# Tube_Driver.net
KiCad netlist of a schematic drawn in Altium Designer
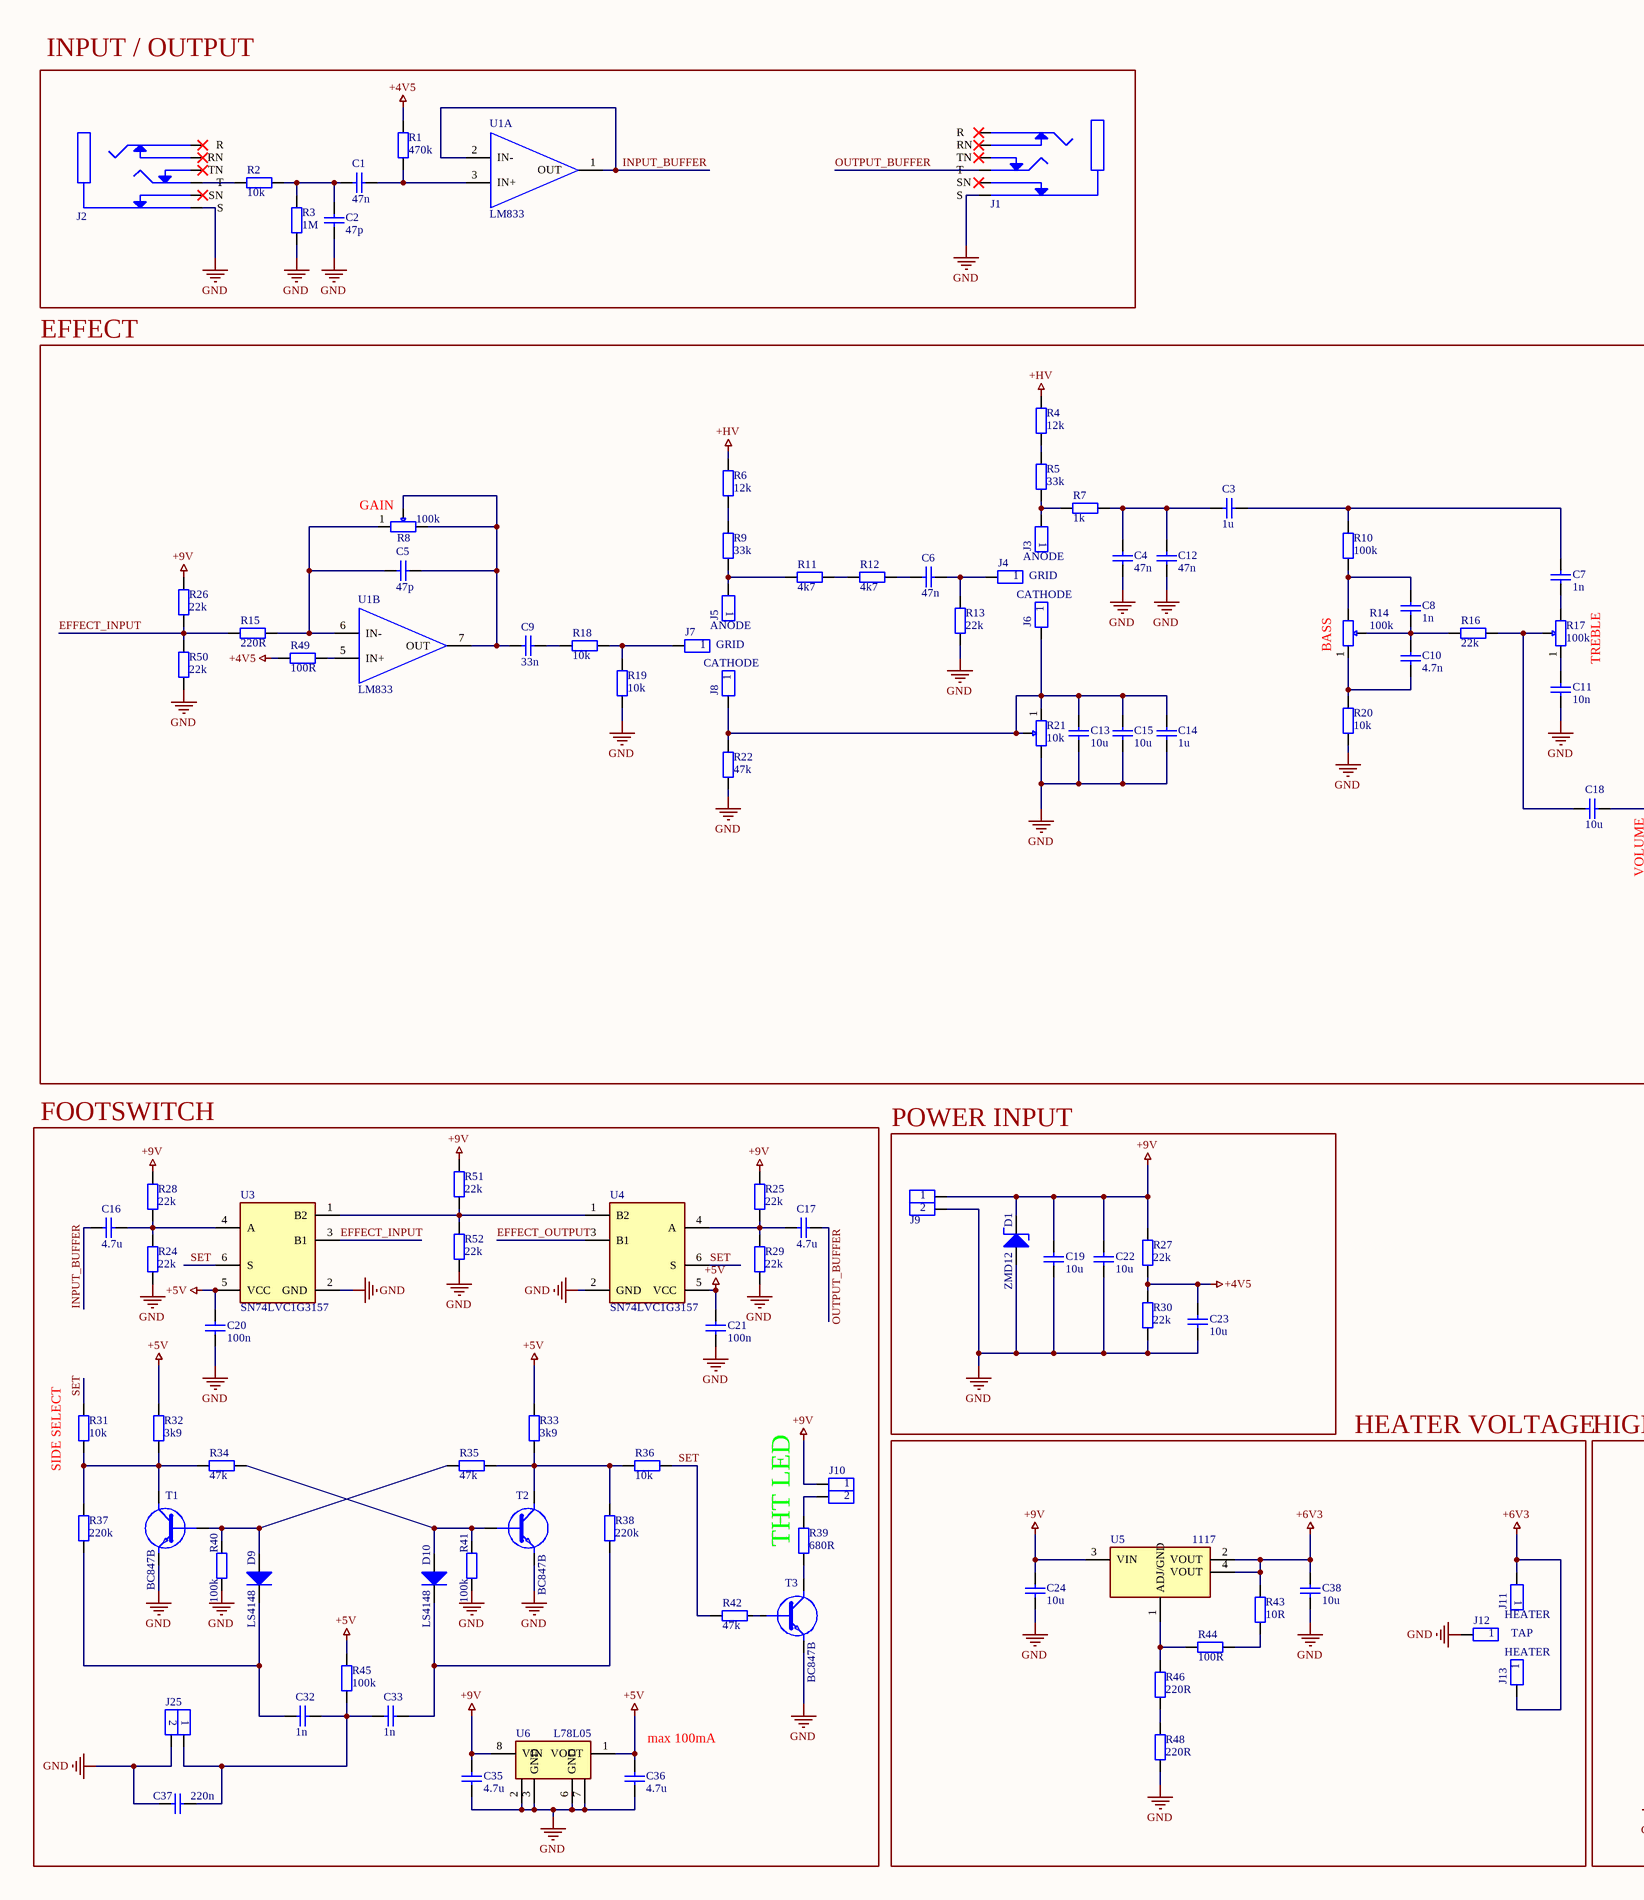
[diagram p0: Tube_Driver.SchDoc, left]
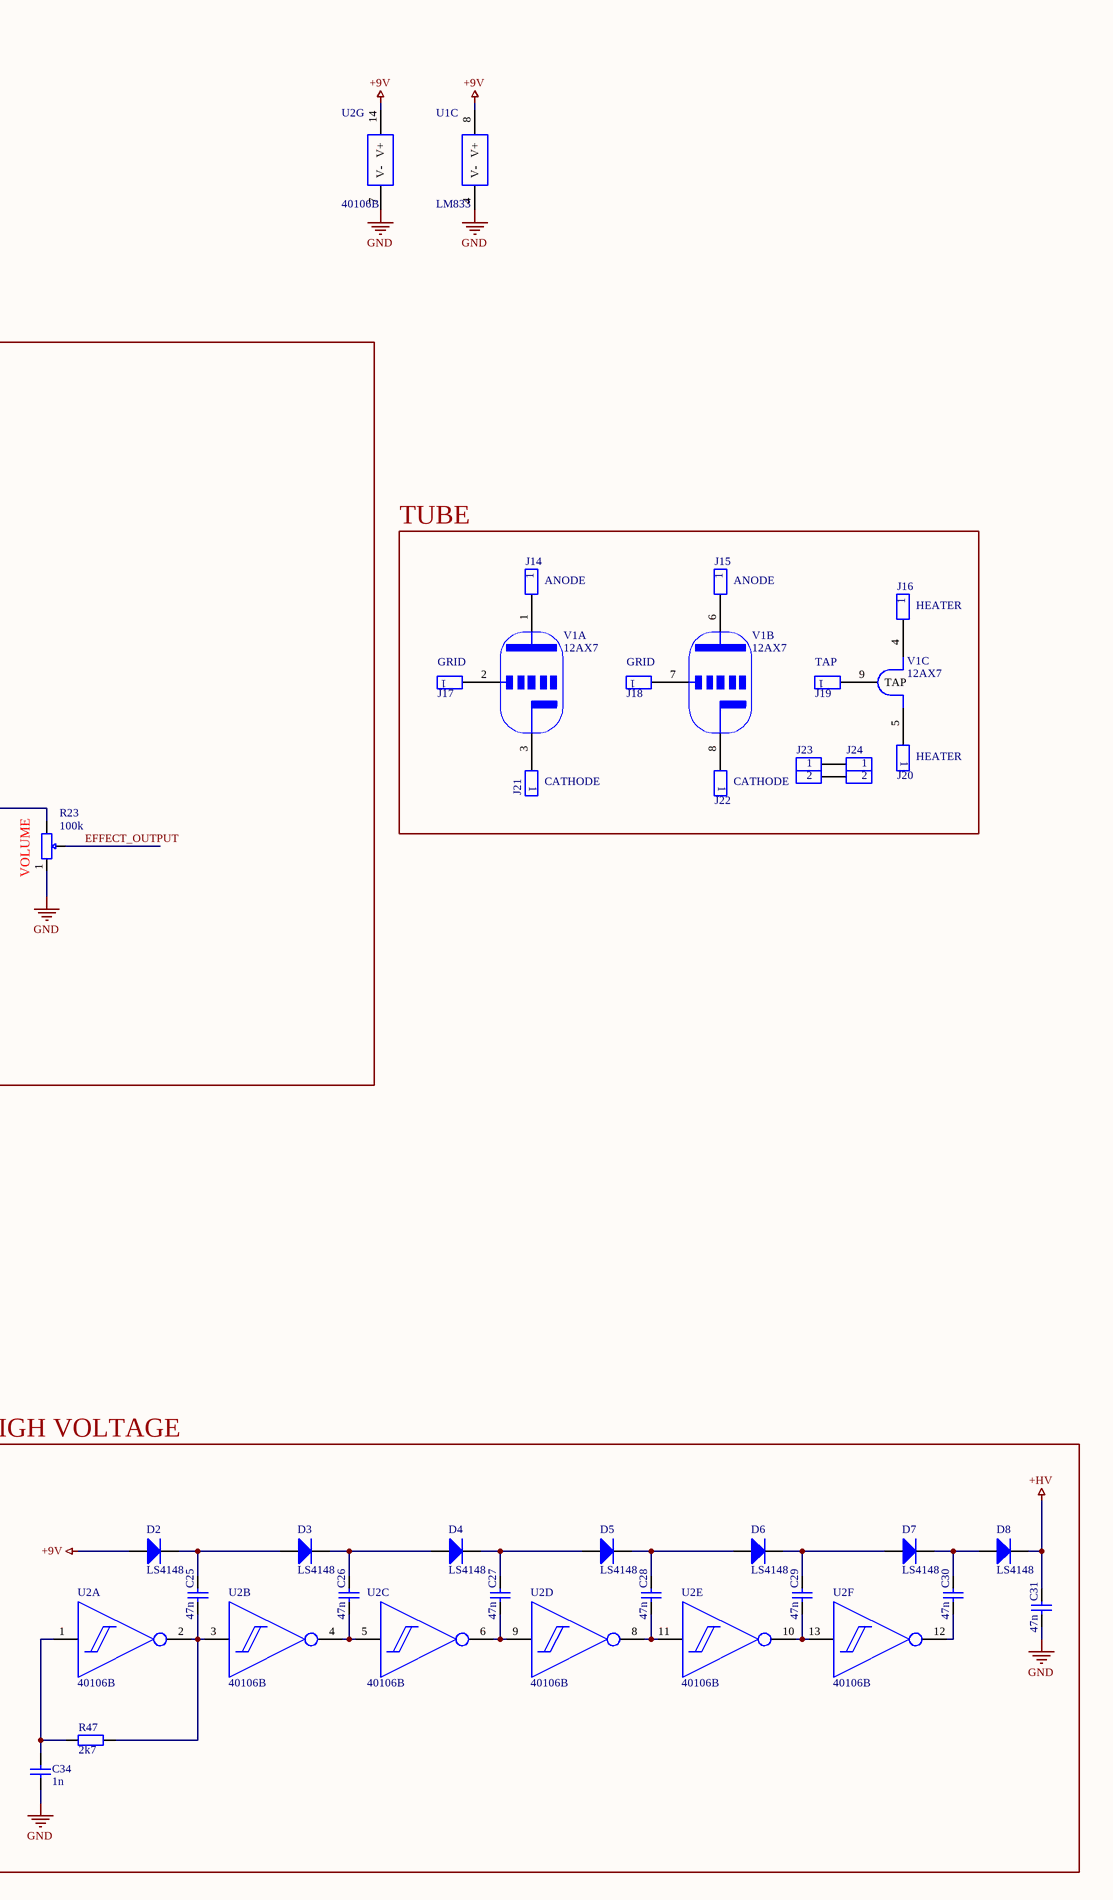
[diagram p1: Tube_Driver.SchDoc, right]

(export (version "E")
  (design (tool "Eeschema 10.0.6"))
  (components
    (comp (ref "C1")
      (value "47n")
      (footprint "TME:CAPACITOR 0805")
      (description "Capacitor: ceramic; MLCC; 47nF; 50V; X7R; ±10%; SMD; 0805")
      (fields
        (field (name "MANUFACTURER") "YAGEO")
        (field (name "MANUFACTURER PART NUMBER") "CC0805KRX7R9BB473")
      )
      (libsource (lib "TME") (part "Capacitor 47n 0805 ±10% SMD E6"))
    )
    (comp (ref "C2")
      (value "47p")
      (footprint "TME:CAPACITOR 0805")
      (description "Capacitor: ceramic; MLCC; 47pF; 50V; C0G (NP0); ±5%; SMD; 0805")
      (fields
        (field (name "MANUFACTURER") "YAGEO")
        (field (name "MANUFACTURER PART NUMBER") "CC0805JRNPO9BN470")
      )
      (libsource (lib "TME") (part "Capacitor 47p 0805 ±5% SMD E6"))
    )
    (comp (ref "C3")
      (value "1u")
      (footprint "TME:CAPACITOR 1206")
      (description "Capacitor: ceramic; MLCC; 1uF; 100V; X7R; ±10%; SMD; 1206")
      (fields
        (field (name "MANUFACTURER") "WALSIN")
        (field (name "MANUFACTURER PART NUMBER") "1206B105K101CT")
      )
      (libsource (lib "TME") (part "Capacitor 1u 1206 ±5% SMD E6"))
    )
    (comp (ref "C4")
      (value "47n")
      (footprint "TME:CAPACITOR 1206")
      (description "Capacitor: ceramic; MLCC; 47nF; 100V; X7R; ±10%; SMD; 1206")
      (fields
        (field (name "MANUFACTURER") "YAGEO")
        (field (name "MANUFACTURER PART NUMBER") "CC1206KRX7R0BB473")
      )
      (libsource (lib "TME") (part "Capacitor 47n 1206 ±10% SMD E6"))
    )
    (comp (ref "C5")
      (value "47p")
      (footprint "TME:CAPACITOR 0805")
      (description "Capacitor: ceramic; MLCC; 47pF; 50V; C0G (NP0); ±5%; SMD; 0805")
      (fields
        (field (name "MANUFACTURER") "YAGEO")
        (field (name "MANUFACTURER PART NUMBER") "CC0805JRNPO9BN470")
      )
      (libsource (lib "TME") (part "Capacitor 47p 0805 ±5% SMD E6"))
    )
    (comp (ref "C6")
      (value "47n")
      (footprint "TME:CAPACITOR 1206")
      (description "Capacitor: ceramic; MLCC; 47nF; 100V; X7R; ±10%; SMD; 1206")
      (fields
        (field (name "MANUFACTURER") "YAGEO")
        (field (name "MANUFACTURER PART NUMBER") "CC1206KRX7R0BB473")
      )
      (libsource (lib "TME") (part "Capacitor 47n 1206 ±10% SMD E6"))
    )
    (comp (ref "C7")
      (value "1n")
      (footprint "TME:CAPACITOR 0805")
      (description "Capacitor: ceramic; MLCC; 1nF; 50V; X7R; ±10%; SMD; 0805")
      (fields
        (field (name "MANUFACTURER") "YAGEO")
        (field (name "MANUFACTURER PART NUMBER") "CC0805KRX7R9BB102")
      )
      (libsource (lib "TME") (part "Capacitor 1n 0805 ±10% SMD E6"))
    )
    (comp (ref "C8")
      (value "1n")
      (footprint "TME:CAPACITOR 0805")
      (description "Capacitor: ceramic; MLCC; 1nF; 50V; X7R; ±10%; SMD; 0805")
      (fields
        (field (name "MANUFACTURER") "YAGEO")
        (field (name "MANUFACTURER PART NUMBER") "CC0805KRX7R9BB102")
      )
      (libsource (lib "TME") (part "Capacitor 1n 0805 ±10% SMD E6"))
    )
    (comp (ref "C9")
      (value "33n")
      (footprint "TME:CAPACITOR 0805")
      (description "Capacitor: ceramic; MLCC; 33nF; 50V; X7R; ±10%; SMD; 0805")
      (fields
        (field (name "MANUFACTURER") "YAGEO")
        (field (name "MANUFACTURER PART NUMBER") "CC0805KRX7R9BB333")
      )
      (libsource (lib "TME") (part "Capacitor 33n 0805 ±10% SMD E6"))
    )
    (comp (ref "C10")
      (value "4.7n")
      (footprint "TME:CAPACITOR 0805")
      (description "Capacitor: ceramic; MLCC; 4.7nF; 50V; X7R; ±10%; SMD; 0805")
      (fields
        (field (name "MANUFACTURER") "YAGEO")
        (field (name "MANUFACTURER PART NUMBER") "CC0805KRX7R9BB472")
      )
      (libsource (lib "TME") (part "Capacitor 4n7 0805 ±10% SMD E6"))
    )
    (comp (ref "C11")
      (value "10n")
      (footprint "TME:CAPACITOR 0805")
      (description "Capacitor: ceramic; MLCC; 10nF; 50V; X7R; ±10%; SMD; 0805")
      (fields
        (field (name "MANUFACTURER") "YAGEO")
        (field (name "MANUFACTURER PART NUMBER") "CC0805KRX7R9BB103")
      )
      (libsource (lib "TME") (part "Capacitor 10n 0805 ±10% SMD E6"))
    )
    (comp (ref "C12")
      (value "47n")
      (footprint "TME:CAPACITOR 1206")
      (description "Capacitor: ceramic; MLCC; 47nF; 100V; X7R; ±10%; SMD; 1206")
      (fields
        (field (name "MANUFACTURER") "YAGEO")
        (field (name "MANUFACTURER PART NUMBER") "CC1206KRX7R0BB473")
      )
      (libsource (lib "TME") (part "Capacitor 47n 1206 ±10% SMD E6"))
    )
    (comp (ref "C13")
      (value "10u")
      (footprint "TME:CAPACITOR 0805")
      (description "Capacitor: ceramic; MLCC; 10uF; 25V; X5R; ±10%; SMD; 0805")
      (fields
        (field (name "MANUFACTURER") "MURATA")
        (field (name "MANUFACTURER PART NUMBER") "GRJ21BR61E106KE01K")
      )
      (libsource (lib "TME") (part "Capacitor 10u 0805 ±10% SMD E3"))
    )
    (comp (ref "C14")
      (value "1u")
      (footprint "TME:CAPACITOR 0805")
      (description "Capacitor: ceramic; MLCC; 1uF; 16V; X7R; ±10%; SMD; 0805")
      (fields
        (field (name "MANUFACTURER") "YAGEO")
        (field (name "MANUFACTURER PART NUMBER") "CC0805KKX7R7BB105")
      )
      (libsource (lib "TME") (part "Capacitor 1u 0805 ±10% SMD E3"))
    )
    (comp (ref "C15")
      (value "10u")
      (footprint "TME:CAPACITOR 0805")
      (description "Capacitor: ceramic; MLCC; 10uF; 25V; X5R; ±10%; SMD; 0805")
      (fields
        (field (name "MANUFACTURER") "MURATA")
        (field (name "MANUFACTURER PART NUMBER") "GRJ21BR61E106KE01K")
      )
      (libsource (lib "TME") (part "Capacitor 10u 0805 ±10% SMD E3"))
    )
    (comp (ref "C16")
      (value "4.7u")
      (footprint "TME:CAPACITOR 0805")
      (description "Capacitor: ceramic; MLCC; 4.7uF; 16V; X7R; ±10%; SMD; 0805")
      (fields
        (field (name "MANUFACTURER") "YAGEO")
        (field (name "MANUFACTURER PART NUMBER") "CC0805KKX7R7BB475")
      )
      (libsource (lib "TME") (part "Capacitor 4u7 0805 ±10% SMD E3"))
    )
    (comp (ref "C17")
      (value "4.7u")
      (footprint "TME:CAPACITOR 0805")
      (description "Capacitor: ceramic; MLCC; 4.7uF; 16V; X7R; ±10%; SMD; 0805")
      (fields
        (field (name "MANUFACTURER") "YAGEO")
        (field (name "MANUFACTURER PART NUMBER") "CC0805KKX7R7BB475")
      )
      (libsource (lib "TME") (part "Capacitor 4u7 0805 ±10% SMD E3"))
    )
    (comp (ref "C18")
      (value "10u")
      (footprint "TME:CAPACITOR 0805")
      (description "Capacitor: ceramic; MLCC; 10uF; 25V; X5R; ±10%; SMD; 0805")
      (fields
        (field (name "MANUFACTURER") "MURATA")
        (field (name "MANUFACTURER PART NUMBER") "GRJ21BR61E106KE01K")
      )
      (libsource (lib "TME") (part "Capacitor 10u 0805 ±10% SMD E3"))
    )
    (comp (ref "C19")
      (value "10u")
      (footprint "TME:CAPACITOR 0805")
      (description "Capacitor: ceramic; MLCC; 10uF; 25V; X5R; ±10%; SMD; 0805")
      (fields
        (field (name "MANUFACTURER") "MURATA")
        (field (name "MANUFACTURER PART NUMBER") "GRJ21BR61E106KE01K")
      )
      (libsource (lib "TME") (part "Capacitor 10u 0805 ±10% SMD E3"))
    )
    (comp (ref "C20")
      (value "100n")
      (footprint "TME:CAPACITOR 0805")
      (description "Capacitor: ceramic; MLCC; 100nF; 50V; X7R; ±10%; SMD; 0805")
      (fields
        (field (name "MANUFACTURER") "YAGEO")
        (field (name "MANUFACTURER PART NUMBER") "CC0805KRX7R9BB104")
      )
      (libsource (lib "TME") (part "Capacitor 100n 0805 ±10% SMD E6"))
    )
    (comp (ref "C21")
      (value "100n")
      (footprint "TME:CAPACITOR 0805")
      (description "Capacitor: ceramic; MLCC; 100nF; 50V; X7R; ±10%; SMD; 0805")
      (fields
        (field (name "MANUFACTURER") "YAGEO")
        (field (name "MANUFACTURER PART NUMBER") "CC0805KRX7R9BB104")
      )
      (libsource (lib "TME") (part "Capacitor 100n 0805 ±10% SMD E6"))
    )
    (comp (ref "C22")
      (value "10u")
      (footprint "TME:CAPACITOR 0805")
      (description "Capacitor: ceramic; MLCC; 10uF; 25V; X5R; ±10%; SMD; 0805")
      (fields
        (field (name "MANUFACTURER") "MURATA")
        (field (name "MANUFACTURER PART NUMBER") "GRJ21BR61E106KE01K")
      )
      (libsource (lib "TME") (part "Capacitor 10u 0805 ±10% SMD E3"))
    )
    (comp (ref "C23")
      (value "10u")
      (footprint "TME:CAPACITOR 0805")
      (description "Capacitor: ceramic; MLCC; 10uF; 25V; X5R; ±10%; SMD; 0805")
      (fields
        (field (name "MANUFACTURER") "MURATA")
        (field (name "MANUFACTURER PART NUMBER") "GRJ21BR61E106KE01K")
      )
      (libsource (lib "TME") (part "Capacitor 10u 0805 ±10% SMD E3"))
    )
    (comp (ref "C24")
      (value "10u")
      (footprint "TME:CAPACITOR 0805")
      (description "Capacitor: ceramic; MLCC; 10uF; 25V; X5R; ±10%; SMD; 0805")
      (fields
        (field (name "MANUFACTURER") "MURATA")
        (field (name "MANUFACTURER PART NUMBER") "GRJ21BR61E106KE01K")
      )
      (libsource (lib "TME") (part "Capacitor 10u 0805 ±10% SMD E3"))
    )
    (comp (ref "C25")
      (value "47n")
      (footprint "TME:CAPACITOR 1206")
      (description "Capacitor: ceramic; MLCC; 47nF; 100V; X7R; ±10%; SMD; 1206")
      (fields
        (field (name "MANUFACTURER") "YAGEO")
        (field (name "MANUFACTURER PART NUMBER") "CC1206KRX7R0BB473")
      )
      (libsource (lib "TME") (part "Capacitor 47n 1206 ±10% SMD E6"))
    )
    (comp (ref "C26")
      (value "47n")
      (footprint "TME:CAPACITOR 1206")
      (description "Capacitor: ceramic; MLCC; 47nF; 100V; X7R; ±10%; SMD; 1206")
      (fields
        (field (name "MANUFACTURER") "YAGEO")
        (field (name "MANUFACTURER PART NUMBER") "CC1206KRX7R0BB473")
      )
      (libsource (lib "TME") (part "Capacitor 47n 1206 ±10% SMD E6"))
    )
    (comp (ref "C27")
      (value "47n")
      (footprint "TME:CAPACITOR 1206")
      (description "Capacitor: ceramic; MLCC; 47nF; 100V; X7R; ±10%; SMD; 1206")
      (fields
        (field (name "MANUFACTURER") "YAGEO")
        (field (name "MANUFACTURER PART NUMBER") "CC1206KRX7R0BB473")
      )
      (libsource (lib "TME") (part "Capacitor 47n 1206 ±10% SMD E6"))
    )
    (comp (ref "C28")
      (value "47n")
      (footprint "TME:CAPACITOR 1206")
      (description "Capacitor: ceramic; MLCC; 47nF; 100V; X7R; ±10%; SMD; 1206")
      (fields
        (field (name "MANUFACTURER") "YAGEO")
        (field (name "MANUFACTURER PART NUMBER") "CC1206KRX7R0BB473")
      )
      (libsource (lib "TME") (part "Capacitor 47n 1206 ±10% SMD E6"))
    )
    (comp (ref "C29")
      (value "47n")
      (footprint "TME:CAPACITOR 1206")
      (description "Capacitor: ceramic; MLCC; 47nF; 100V; X7R; ±10%; SMD; 1206")
      (fields
        (field (name "MANUFACTURER") "YAGEO")
        (field (name "MANUFACTURER PART NUMBER") "CC1206KRX7R0BB473")
      )
      (libsource (lib "TME") (part "Capacitor 47n 1206 ±10% SMD E6"))
    )
    (comp (ref "C30")
      (value "47n")
      (footprint "TME:CAPACITOR 1206")
      (description "Capacitor: ceramic; MLCC; 47nF; 100V; X7R; ±10%; SMD; 1206")
      (fields
        (field (name "MANUFACTURER") "YAGEO")
        (field (name "MANUFACTURER PART NUMBER") "CC1206KRX7R0BB473")
      )
      (libsource (lib "TME") (part "Capacitor 47n 1206 ±10% SMD E6"))
    )
    (comp (ref "C31")
      (value "47n")
      (footprint "TME:CAPACITOR 1206")
      (description "Capacitor: ceramic; MLCC; 47nF; 100V; X7R; ±10%; SMD; 1206")
      (fields
        (field (name "MANUFACTURER") "YAGEO")
        (field (name "MANUFACTURER PART NUMBER") "CC1206KRX7R0BB473")
      )
      (libsource (lib "TME") (part "Capacitor 47n 1206 ±10% SMD E6"))
    )
    (comp (ref "C32")
      (value "1n")
      (footprint "TME:CAPACITOR 0805")
      (description "Capacitor: ceramic; MLCC; 1nF; 50V; X7R; ±10%; SMD; 0805")
      (fields
        (field (name "MANUFACTURER") "YAGEO")
        (field (name "MANUFACTURER PART NUMBER") "CC0805KRX7R9BB102")
      )
      (libsource (lib "TME") (part "Capacitor 1n 0805 ±10% SMD E6"))
    )
    (comp (ref "C33")
      (value "1n")
      (footprint "TME:CAPACITOR 0805")
      (description "Capacitor: ceramic; MLCC; 1nF; 50V; X7R; ±10%; SMD; 0805")
      (fields
        (field (name "MANUFACTURER") "YAGEO")
        (field (name "MANUFACTURER PART NUMBER") "CC0805KRX7R9BB102")
      )
      (libsource (lib "TME") (part "Capacitor 1n 0805 ±10% SMD E6"))
    )
    (comp (ref "C34")
      (value "1n")
      (footprint "TME:CAPACITOR 0805")
      (description "Capacitor: ceramic; MLCC; 1nF; 50V; X7R; ±10%; SMD; 0805")
      (fields
        (field (name "MANUFACTURER") "YAGEO")
        (field (name "MANUFACTURER PART NUMBER") "CC0805KRX7R9BB102")
      )
      (libsource (lib "TME") (part "Capacitor 1n 0805 ±10% SMD E6"))
    )
    (comp (ref "C35")
      (value "4.7u")
      (footprint "TME:CAPACITOR 0805")
      (description "Capacitor: ceramic; MLCC; 4.7uF; 16V; X7R; ±10%; SMD; 0805")
      (fields
        (field (name "MANUFACTURER") "YAGEO")
        (field (name "MANUFACTURER PART NUMBER") "CC0805KKX7R7BB475")
      )
      (libsource (lib "TME") (part "Capacitor 4u7 0805 ±10% SMD E3"))
    )
    (comp (ref "C36")
      (value "4.7u")
      (footprint "TME:CAPACITOR 0805")
      (description "Capacitor: ceramic; MLCC; 4.7uF; 16V; X7R; ±10%; SMD; 0805")
      (fields
        (field (name "MANUFACTURER") "YAGEO")
        (field (name "MANUFACTURER PART NUMBER") "CC0805KKX7R7BB475")
      )
      (libsource (lib "TME") (part "Capacitor 4u7 0805 ±10% SMD E3"))
    )
    (comp (ref "C37")
      (value "220n")
      (footprint "TME:CAPACITOR 0805")
      (description "Capacitor: ceramic; MLCC; 220nF; 50V; X7R; ±10%; SMD; 0805")
      (fields
        (field (name "MANUFACTURER") "YAGEO")
        (field (name "MANUFACTURER PART NUMBER") "CC0805KKX7R9BB224")
      )
      (libsource (lib "TME") (part "Capacitor 220n 0805 ±10% SMD E6"))
    )
    (comp (ref "C38")
      (value "10u")
      (footprint "TME:CAPACITOR 0805")
      (description "Capacitor: ceramic; MLCC; 10uF; 25V; X5R; ±10%; SMD; 0805")
      (fields
        (field (name "MANUFACTURER") "MURATA")
        (field (name "MANUFACTURER PART NUMBER") "GRJ21BR61E106KE01K")
      )
      (libsource (lib "TME") (part "Capacitor 10u 0805 ±10% SMD E3"))
    )
    (comp (ref "D1")
      (value "ZMD12")
      (footprint "TME:DIODE SOD-80 DO-231AA")
      (description "Diode: Zener; 1W; 12V; SMD; reel,tape; MiniMELF plastic")
      (fields (field (name "MANUFACTURER") "DIOTEC SEMICONDUCTOR") (field (name "POWER") "1W"))
      (libsource (lib "TME") (part "Diode 12V 1W SOD80 Zener ZMD12"))
    )
    (comp (ref "D2")
      (value "LS4148")
      (footprint "TME:DIODE SOD-80 DO-231AA")
      (description "Diode: switching; SMD; 100V; 0.15A; 4ns; MiniMELF quadro; Ufmax: 1V")
      (fields (field (name "MANUFACTURER") "DIOTEC SEMICONDUCTOR"))
      (libsource (lib "TME") (part "Diode 100V 0.15A SOD80 General Purpose LL4148"))
    )
    (comp (ref "D3")
      (value "LS4148")
      (footprint "TME:DIODE SOD-80 DO-231AA")
      (description "Diode: switching; SMD; 100V; 0.15A; 4ns; MiniMELF quadro; Ufmax: 1V")
      (fields (field (name "MANUFACTURER") "DIOTEC SEMICONDUCTOR"))
      (libsource (lib "TME") (part "Diode 100V 0.15A SOD80 General Purpose LL4148"))
    )
    (comp (ref "D4")
      (value "LS4148")
      (footprint "TME:DIODE SOD-80 DO-231AA")
      (description "Diode: switching; SMD; 100V; 0.15A; 4ns; MiniMELF quadro; Ufmax: 1V")
      (fields (field (name "MANUFACTURER") "DIOTEC SEMICONDUCTOR"))
      (libsource (lib "TME") (part "Diode 100V 0.15A SOD80 General Purpose LL4148"))
    )
    (comp (ref "D5")
      (value "LS4148")
      (footprint "TME:DIODE SOD-80 DO-231AA")
      (description "Diode: switching; SMD; 100V; 0.15A; 4ns; MiniMELF quadro; Ufmax: 1V")
      (fields (field (name "MANUFACTURER") "DIOTEC SEMICONDUCTOR"))
      (libsource (lib "TME") (part "Diode 100V 0.15A SOD80 General Purpose LL4148"))
    )
    (comp (ref "D6")
      (value "LS4148")
      (footprint "TME:DIODE SOD-80 DO-231AA")
      (description "Diode: switching; SMD; 100V; 0.15A; 4ns; MiniMELF quadro; Ufmax: 1V")
      (fields (field (name "MANUFACTURER") "DIOTEC SEMICONDUCTOR"))
      (libsource (lib "TME") (part "Diode 100V 0.15A SOD80 General Purpose LL4148"))
    )
    (comp (ref "D7")
      (value "LS4148")
      (footprint "TME:DIODE SOD-80 DO-231AA")
      (description "Diode: switching; SMD; 100V; 0.15A; 4ns; MiniMELF quadro; Ufmax: 1V")
      (fields (field (name "MANUFACTURER") "DIOTEC SEMICONDUCTOR"))
      (libsource (lib "TME") (part "Diode 100V 0.15A SOD80 General Purpose LL4148"))
    )
    (comp (ref "D8")
      (value "LS4148")
      (footprint "TME:DIODE SOD-80 DO-231AA")
      (description "Diode: switching; SMD; 100V; 0.15A; 4ns; MiniMELF quadro; Ufmax: 1V")
      (fields (field (name "MANUFACTURER") "DIOTEC SEMICONDUCTOR"))
      (libsource (lib "TME") (part "Diode 100V 0.15A SOD80 General Purpose LL4148"))
    )
    (comp (ref "D9")
      (value "LS4148")
      (footprint "TME:DIODE SOD-80 DO-231AA")
      (description "Diode: switching; SMD; 100V; 0.15A; 4ns; MiniMELF quadro; Ufmax: 1V")
      (fields (field (name "MANUFACTURER") "DIOTEC SEMICONDUCTOR"))
      (libsource (lib "TME") (part "Diode 100V 0.15A SOD80 General Purpose LL4148"))
    )
    (comp (ref "D10")
      (value "LS4148")
      (footprint "TME:DIODE SOD-80 DO-231AA")
      (description "Diode: switching; SMD; 100V; 0.15A; 4ns; MiniMELF quadro; Ufmax: 1V")
      (fields (field (name "MANUFACTURER") "DIOTEC SEMICONDUCTOR"))
      (libsource (lib "TME") (part "Diode 100V 0.15A SOD80 General Purpose LL4148"))
    )
    (comp (ref "J1")
      (value "ACJM-IH")
      (footprint "TME:AMPHENOL ACJM-MHDR")
      (description "Socket; Jack 6,3mm; female; mono,with double switch; ways: 2; THT")
      (fields (field (name "MANUFACTURER") "AMPHENOL"))
      (libsource (lib "TME") (part "Mechanical Jack 6.3mm Socket PCB THT ACJM-MHDR"))
    )
    (comp (ref "J2")
      (value "ACJM-IH")
      (footprint "TME:AMPHENOL ACJM-MHDR")
      (description "Socket; Jack 6,3mm; female; mono,with double switch; ways: 2; THT")
      (fields (field (name "MANUFACTURER") "AMPHENOL"))
      (libsource (lib "TME") (part "Mechanical Jack 6.3mm Socket PCB THT ACJM-MHDR"))
    )
    (comp (ref "J3")
      (value "901200761")
      (footprint "TME:MECHANICAL PINHEADER 1P 2.54MM MALE")
      (description "Pin header; pin strips; C-Grid III; male; PIN: 1; straight; 2.54mm")
      (fields (field (name "MANUFACTURER") "MOLEX"))
      (libsource (lib "TME") (part "Mechanical Pinheader Male 1pin P=2.54mm THT"))
    )
    (comp (ref "J4")
      (value "901200761")
      (footprint "TME:MECHANICAL PINHEADER 1P 2.54MM MALE")
      (description "Pin header; pin strips; C-Grid III; male; PIN: 1; straight; 2.54mm")
      (fields (field (name "MANUFACTURER") "MOLEX"))
      (libsource (lib "") (part "Mechanical Pinheader Male 1pin P=2.54mm THT_3"))
    )
    (comp (ref "J5")
      (value "901200761")
      (footprint "TME:MECHANICAL PINHEADER 1P 2.54MM MALE")
      (description "Pin header; pin strips; C-Grid III; male; PIN: 1; straight; 2.54mm")
      (fields (field (name "MANUFACTURER") "MOLEX"))
      (libsource (lib "TME") (part "Mechanical Pinheader Male 1pin P=2.54mm THT"))
    )
    (comp (ref "J6")
      (value "901200761")
      (footprint "TME:MECHANICAL PINHEADER 1P 2.54MM MALE")
      (description "Pin header; pin strips; C-Grid III; male; PIN: 1; straight; 2.54mm")
      (fields (field (name "MANUFACTURER") "MOLEX"))
      (libsource (lib "") (part "Mechanical Pinheader Male 1pin P=2.54mm THT_1"))
    )
    (comp (ref "J7")
      (value "901200761")
      (footprint "TME:MECHANICAL PINHEADER 1P 2.54MM MALE")
      (description "Pin header; pin strips; C-Grid III; male; PIN: 1; straight; 2.54mm")
      (fields (field (name "MANUFACTURER") "MOLEX"))
      (libsource (lib "") (part "Mechanical Pinheader Male 1pin P=2.54mm THT_3"))
    )
    (comp (ref "J8")
      (value "901200761")
      (footprint "TME:MECHANICAL PINHEADER 1P 2.54MM MALE")
      (description "Pin header; pin strips; C-Grid III; male; PIN: 1; straight; 2.54mm")
      (fields (field (name "MANUFACTURER") "MOLEX"))
      (libsource (lib "") (part "Mechanical Pinheader Male 1pin P=2.54mm THT_1"))
    )
    (comp (ref "J9")
      (value "901200762")
      (footprint "TME:MECHANICAL PINHEADER 2P 2.54MM MALE")
      (description "Pin header; pin strips; C-Grid III; male; PIN: 2; straight; 2.54mm")
      (fields (field (name "MANUFACTURER") "MOLEX"))
      (libsource (lib "") (part "Mechanical Pinheader Male 2pin P=2.54mm THT_1"))
    )
    (comp (ref "J10")
      (value "901200762")
      (footprint "TME:MECHANICAL PINHEADER 2P 2.54MM MALE")
      (description "Pin header; pin strips; C-Grid III; male; PIN: 2; straight; 2.54mm")
      (fields (field (name "MANUFACTURER") "MOLEX"))
      (libsource (lib "TME") (part "Mechanical Pinheader Male 2pin P=2.54mm THT"))
    )
    (comp (ref "J11")
      (value "901200761")
      (footprint "TME:MECHANICAL PINHEADER 1P 2.54MM MALE")
      (description "Pin header; pin strips; C-Grid III; male; PIN: 1; straight; 2.54mm")
      (fields (field (name "MANUFACTURER") "MOLEX"))
      (libsource (lib "TME") (part "Mechanical Pinheader Male 1pin P=2.54mm THT"))
    )
    (comp (ref "J12")
      (value "901200761")
      (footprint "TME:MECHANICAL PINHEADER 1P 2.54MM MALE")
      (description "Pin header; pin strips; C-Grid III; male; PIN: 1; straight; 2.54mm")
      (fields (field (name "MANUFACTURER") "MOLEX"))
      (libsource (lib "") (part "Mechanical Pinheader Male 1pin P=2.54mm THT_3"))
    )
    (comp (ref "J13")
      (value "901200761")
      (footprint "TME:MECHANICAL PINHEADER 1P 2.54MM MALE")
      (description "Pin header; pin strips; C-Grid III; male; PIN: 1; straight; 2.54mm")
      (fields (field (name "MANUFACTURER") "MOLEX"))
      (libsource (lib "") (part "Mechanical Pinheader Male 1pin P=2.54mm THT_1"))
    )
    (comp (ref "J14")
      (value "901200761")
      (footprint "TME:MECHANICAL PINHEADER 1P 2.54MM MALE")
      (description "Pin header; pin strips; C-Grid III; male; PIN: 1; straight; 2.54mm")
      (fields (field (name "MANUFACTURER") "MOLEX"))
      (libsource (lib "") (part "Mechanical Pinheader Male 1pin P=2.54mm THT_1"))
    )
    (comp (ref "J15")
      (value "901200761")
      (footprint "TME:MECHANICAL PINHEADER 1P 2.54MM MALE")
      (description "Pin header; pin strips; C-Grid III; male; PIN: 1; straight; 2.54mm")
      (fields (field (name "MANUFACTURER") "MOLEX"))
      (libsource (lib "") (part "Mechanical Pinheader Male 1pin P=2.54mm THT_1"))
    )
    (comp (ref "J16")
      (value "901200761")
      (footprint "TME:MECHANICAL PINHEADER 1P 2.54MM MALE")
      (description "Pin header; pin strips; C-Grid III; male; PIN: 1; straight; 2.54mm")
      (fields (field (name "MANUFACTURER") "MOLEX"))
      (libsource (lib "") (part "Mechanical Pinheader Male 1pin P=2.54mm THT_1"))
    )
    (comp (ref "J17")
      (value "901200761")
      (footprint "TME:MECHANICAL PINHEADER 1P 2.54MM MALE")
      (description "Pin header; pin strips; C-Grid III; male; PIN: 1; straight; 2.54mm")
      (fields (field (name "MANUFACTURER") "MOLEX"))
      (libsource (lib "") (part "Mechanical Pinheader Male 1pin P=2.54mm THT_2"))
    )
    (comp (ref "J18")
      (value "901200761")
      (footprint "TME:MECHANICAL PINHEADER 1P 2.54MM MALE")
      (description "Pin header; pin strips; C-Grid III; male; PIN: 1; straight; 2.54mm")
      (fields (field (name "MANUFACTURER") "MOLEX"))
      (libsource (lib "") (part "Mechanical Pinheader Male 1pin P=2.54mm THT_2"))
    )
    (comp (ref "J19")
      (value "901200761")
      (footprint "TME:MECHANICAL PINHEADER 1P 2.54MM MALE")
      (description "Pin header; pin strips; C-Grid III; male; PIN: 1; straight; 2.54mm")
      (fields (field (name "MANUFACTURER") "MOLEX"))
      (libsource (lib "") (part "Mechanical Pinheader Male 1pin P=2.54mm THT_2"))
    )
    (comp (ref "J20")
      (value "901200761")
      (footprint "TME:MECHANICAL PINHEADER 1P 2.54MM MALE")
      (description "Pin header; pin strips; C-Grid III; male; PIN: 1; straight; 2.54mm")
      (fields (field (name "MANUFACTURER") "MOLEX"))
      (libsource (lib "TME") (part "Mechanical Pinheader Male 1pin P=2.54mm THT"))
    )
    (comp (ref "J21")
      (value "901200761")
      (footprint "TME:MECHANICAL PINHEADER 1P 2.54MM MALE")
      (description "Pin header; pin strips; C-Grid III; male; PIN: 1; straight; 2.54mm")
      (fields (field (name "MANUFACTURER") "MOLEX"))
      (libsource (lib "TME") (part "Mechanical Pinheader Male 1pin P=2.54mm THT"))
    )
    (comp (ref "J22")
      (value "901200761")
      (footprint "TME:MECHANICAL PINHEADER 1P 2.54MM MALE")
      (description "Pin header; pin strips; C-Grid III; male; PIN: 1; straight; 2.54mm")
      (fields (field (name "MANUFACTURER") "MOLEX"))
      (libsource (lib "TME") (part "Mechanical Pinheader Male 1pin P=2.54mm THT"))
    )
    (comp (ref "J23")
      (value "901200762")
      (footprint "TME:MECHANICAL PINHEADER 2P 2.54MM MALE")
      (description "Pin header; pin strips; C-Grid III; male; PIN: 2; straight; 2.54mm")
      (fields (field (name "MANUFACTURER") "MOLEX"))
      (libsource (lib "") (part "Mechanical Pinheader Male 2pin P=2.54mm THT_1"))
    )
    (comp (ref "J24")
      (value "901200762")
      (footprint "TME:MECHANICAL PINHEADER 2P 2.54MM MALE")
      (description "Pin header; pin strips; C-Grid III; male; PIN: 2; straight; 2.54mm")
      (fields (field (name "MANUFACTURER") "MOLEX"))
      (libsource (lib "TME") (part "Mechanical Pinheader Male 2pin P=2.54mm THT"))
    )
    (comp (ref "J25")
      (value "901200762")
      (footprint "TME:MECHANICAL PINHEADER 2P 2.54MM MALE")
      (description "Pin header; pin strips; C-Grid III; male; PIN: 2; straight; 2.54mm")
      (fields (field (name "MANUFACTURER") "MOLEX"))
      (libsource (lib "TME") (part "Mechanical Pinheader Male 2pin P=2.54mm THT"))
    )
    (comp (ref "R1")
      (value "470k")
      (footprint "TME:RESISTOR 0805")
      (description "Resistor: thick film; SMD; 0805; 470kΩ; 0,125W; ±1%; -55÷155°C")
      (fields
        (field (name "MANUFACTURER") "YAGEO")
        (field (name "MANUFACTURER PART NUMBER") "RC0805FR-07470KL")
      )
      (libsource (lib "TME") (part "Resistor 470k 0805 1% 0.125W SMD E12"))
    )
    (comp (ref "R2")
      (value "10k")
      (footprint "TME:RESISTOR 0805")
      (description "Resistor: thick film; SMD; 0805; 10kΩ; 0,125W; ±1%; -55÷155°C")
      (fields
        (field (name "MANUFACTURER") "YAGEO")
        (field (name "MANUFACTURER PART NUMBER") "RC0805FR-0710KL")
      )
      (libsource (lib "") (part "Resistor 10k 0805 1% 0.125W SMD E12_1"))
    )
    (comp (ref "R3")
      (value "1M")
      (footprint "TME:RESISTOR 0805")
      (description "Resistor: thick film; SMD; 0805; 1MΩ; 0,125W; ±1%; -55÷155°C")
      (fields
        (field (name "MANUFACTURER") "YAGEO")
        (field (name "MANUFACTURER PART NUMBER") "RC0805FR-071ML")
      )
      (libsource (lib "TME") (part "Resistor 1M 0805 1% 0.125W SMD E12"))
    )
    (comp (ref "R4")
      (value "12k")
      (footprint "TME:RESISTOR 0805")
      (description "Resistor: thick film; SMD; 0805; 12kΩ; 0,125W; ±1%; -55÷155°C")
      (fields
        (field (name "MANUFACTURER") "YAGEO")
        (field (name "MANUFACTURER PART NUMBER") "RC0805FR-0712KL")
      )
      (libsource (lib "TME") (part "Resistor 12k 0805 1% 0.125W SMD E12"))
    )
    (comp (ref "R5")
      (value "33k")
      (footprint "TME:RESISTOR 0805")
      (description "Resistor: thick film; SMD; 0805; 33kΩ; 0,125W; ±1%; -55÷155°C")
      (fields
        (field (name "MANUFACTURER") "YAGEO")
        (field (name "MANUFACTURER PART NUMBER") "RC0805FR-0733KL")
      )
      (libsource (lib "TME") (part "Resistor 33k 0805 1% 0.125W SMD E12"))
    )
    (comp (ref "R6")
      (value "12k")
      (footprint "TME:RESISTOR 0805")
      (description "Resistor: thick film; SMD; 0805; 12kΩ; 0,125W; ±1%; -55÷155°C")
      (fields
        (field (name "MANUFACTURER") "YAGEO")
        (field (name "MANUFACTURER PART NUMBER") "RC0805FR-0712KL")
      )
      (libsource (lib "TME") (part "Resistor 12k 0805 1% 0.125W SMD E12"))
    )
    (comp (ref "R7")
      (value "1k")
      (footprint "TME:RESISTOR 0805")
      (description "Resistor: thick film; SMD; 0805; 1kΩ; 0,125W; ±1%; -55÷155°C")
      (fields
        (field (name "MANUFACTURER") "YAGEO")
        (field (name "MANUFACTURER PART NUMBER") "RC0805FR-071KL")
      )
      (libsource (lib "TME") (part "Resistor 1k 0805 1% 0.125W SMD E12"))
    )
    (comp (ref "R8")
      (value "100k")
      (footprint "TME:POTENTIOMETER PTV09A")
      (description "Potentiometer: shaft; single turn; 100kΩ; 125mW; ±20%; THT; 6mm")
      (fields
        (field (name "MANUFACTURER") "SR PASSIVES")
        (field (name "MANUFACTURER PART NUMBER") "R9011-1-100K")
      )
      (libsource (lib "") (part "Potentiometer PCB 100k THT Linear PTV09A_1"))
    )
    (comp (ref "R9")
      (value "33k")
      (footprint "TME:RESISTOR 0805")
      (description "Resistor: thick film; SMD; 0805; 33kΩ; 0,125W; ±1%; -55÷155°C")
      (fields
        (field (name "MANUFACTURER") "YAGEO")
        (field (name "MANUFACTURER PART NUMBER") "RC0805FR-0733KL")
      )
      (libsource (lib "TME") (part "Resistor 33k 0805 1% 0.125W SMD E12"))
    )
    (comp (ref "R10")
      (value "100k")
      (footprint "TME:RESISTOR 0805")
      (description "Resistor: thick film; SMD; 0805; 100kΩ; 0,125W; ±1%; -55÷155°C")
      (fields
        (field (name "MANUFACTURER") "YAGEO")
        (field (name "MANUFACTURER PART NUMBER") "RC0805FR-07100KL")
      )
      (libsource (lib "TME") (part "Resistor 100k 0805 1% 0.125W SMD E12"))
    )
    (comp (ref "R11")
      (value "4k7")
      (footprint "TME:RESISTOR 0805")
      (description "Resistor: thick film; SMD; 0805; 4.7kΩ; 0,125W; ±1%; -55÷155°C")
      (fields
        (field (name "MANUFACTURER") "YAGEO")
        (field (name "MANUFACTURER PART NUMBER") "RC0805FR-074K7L")
      )
      (libsource (lib "TME") (part "Resistor 4k7 0805 1% 0.125W SMD E12"))
    )
    (comp (ref "R12")
      (value "4k7")
      (footprint "TME:RESISTOR 0805")
      (description "Resistor: thick film; SMD; 0805; 4.7kΩ; 0,125W; ±1%; -55÷155°C")
      (fields
        (field (name "MANUFACTURER") "YAGEO")
        (field (name "MANUFACTURER PART NUMBER") "RC0805FR-074K7L")
      )
      (libsource (lib "TME") (part "Resistor 4k7 0805 1% 0.125W SMD E12"))
    )
    (comp (ref "R13")
      (value "22k")
      (footprint "TME:RESISTOR 0805")
      (description "Resistor: thick film; SMD; 0805; 22kΩ; 0,125W; ±1%; -55÷155°C")
      (fields
        (field (name "MANUFACTURER") "YAGEO")
        (field (name "MANUFACTURER PART NUMBER") "RC0805FR-0722KL")
      )
      (libsource (lib "TME") (part "Resistor 22k 0805 1% 0.125W SMD E12"))
    )
    (comp (ref "R14")
      (value "100k")
      (footprint "TME:POTENTIOMETER PTV09A")
      (description "Potentiometer: shaft; single turn; 100kΩ; 125mW; ±20%; THT; 6mm")
      (fields
        (field (name "MANUFACTURER") "SR PASSIVES")
        (field (name "MANUFACTURER PART NUMBER") "R9011-1-100K")
      )
      (libsource (lib "") (part "Potentiometer PCB 100k THT Linear PTV09A_1"))
    )
    (comp (ref "R15")
      (value "220R")
      (footprint "TME:RESISTOR 0805")
      (description "Resistor: thick film; SMD; 0805; 220Ω; 0,125W; ±1%; -55÷155°C")
      (fields
        (field (name "MANUFACTURER") "YAGEO")
        (field (name "MANUFACTURER PART NUMBER") "RC0805FR-07220RL")
      )
      (libsource (lib "") (part "Resistor 220R 0805 1% 0.125W SMD E12_1"))
    )
    (comp (ref "R16")
      (value "22k")
      (footprint "TME:RESISTOR 0805")
      (description "Resistor: thick film; SMD; 0805; 22kΩ; 0,125W; ±1%; -55÷155°C")
      (fields
        (field (name "MANUFACTURER") "YAGEO")
        (field (name "MANUFACTURER PART NUMBER") "RC0805FR-0722KL")
      )
      (libsource (lib "") (part "Resistor 22k 0805 1% 0.125W SMD E12_1"))
    )
    (comp (ref "R17")
      (value "100k")
      (footprint "TME:POTENTIOMETER PTV09A")
      (description "Potentiometer: shaft; single turn; 100kΩ; 125mW; ±20%; THT; 6mm")
      (fields
        (field (name "MANUFACTURER") "SR PASSIVES")
        (field (name "MANUFACTURER PART NUMBER") "R9011-1-100K")
      )
      (libsource (lib "TME") (part "Potentiometer PCB 100k THT Linear PTV09A"))
    )
    (comp (ref "R18")
      (value "10k")
      (footprint "TME:RESISTOR 0805")
      (description "Resistor: thick film; SMD; 0805; 10kΩ; 0,125W; ±1%; -55÷155°C")
      (fields
        (field (name "MANUFACTURER") "YAGEO")
        (field (name "MANUFACTURER PART NUMBER") "RC0805FR-0710KL")
      )
      (libsource (lib "") (part "Resistor 10k 0805 1% 0.125W SMD E12_1"))
    )
    (comp (ref "R19")
      (value "10k")
      (footprint "TME:RESISTOR 0805")
      (description "Resistor: thick film; SMD; 0805; 10kΩ; 0,125W; ±1%; -55÷155°C")
      (fields
        (field (name "MANUFACTURER") "YAGEO")
        (field (name "MANUFACTURER PART NUMBER") "RC0805FR-0710KL")
      )
      (libsource (lib "TME") (part "Resistor 10k 0805 1% 0.125W SMD E12"))
    )
    (comp (ref "R20")
      (value "10k")
      (footprint "TME:RESISTOR 0805")
      (description "Resistor: thick film; SMD; 0805; 10kΩ; 0,125W; ±1%; -55÷155°C")
      (fields
        (field (name "MANUFACTURER") "YAGEO")
        (field (name "MANUFACTURER PART NUMBER") "RC0805FR-0710KL")
      )
      (libsource (lib "TME") (part "Resistor 10k 0805 1% 0.125W SMD E12"))
    )
    (comp (ref "R21")
      (value "10k")
      (footprint "TME:Potentiometer 3x3.5x1.55mm")
      (description "Potentiometer: mounting; single turn; 10kΩ; 100mW; SMD; ±25%; linear")
      (fields
        (field (name "MANUFACTURER") "SR PASSIVES")
        (field (name "MANUFACTURER PART NUMBER") "3305SMD-10K")
      )
      (libsource (lib "TME") (part "Potentiometer 10k 25% 0.1W SMD Linear 3x3.5x1.55mm"))
    )
    (comp (ref "R22")
      (value "47k")
      (footprint "TME:RESISTOR 0805")
      (description "Resistor: thick film; SMD; 0805; 47kΩ; 0,125W; ±1%; -55÷155°C")
      (fields
        (field (name "MANUFACTURER") "YAGEO")
        (field (name "MANUFACTURER PART NUMBER") "RC0805FR-0747KL")
      )
      (libsource (lib "") (part "Resistor 47k 0805 1% 0.125W SMD E12_1"))
    )
    (comp (ref "R23")
      (value "100k")
      (footprint "TME:POTENTIOMETER PTV09A")
      (description "Potentiometer: shaft; single turn; 100kΩ; 125mW; ±20%; THT; 6mm")
      (fields
        (field (name "MANUFACTURER") "SR PASSIVES")
        (field (name "MANUFACTURER PART NUMBER") "R9011-1-100K")
      )
      (libsource (lib "") (part "Potentiometer PCB 100k THT Linear PTV09A_1"))
    )
    (comp (ref "R24")
      (value "22k")
      (footprint "TME:RESISTOR 0805")
      (description "Resistor: thick film; SMD; 0805; 22kΩ; 0,125W; ±1%; -55÷155°C")
      (fields
        (field (name "MANUFACTURER") "YAGEO")
        (field (name "MANUFACTURER PART NUMBER") "RC0805FR-0722KL")
      )
      (libsource (lib "TME") (part "Resistor 22k 0805 1% 0.125W SMD E12"))
    )
    (comp (ref "R25")
      (value "22k")
      (footprint "TME:RESISTOR 0805")
      (description "Resistor: thick film; SMD; 0805; 22kΩ; 0,125W; ±1%; -55÷155°C")
      (fields
        (field (name "MANUFACTURER") "YAGEO")
        (field (name "MANUFACTURER PART NUMBER") "RC0805FR-0722KL")
      )
      (libsource (lib "TME") (part "Resistor 22k 0805 1% 0.125W SMD E12"))
    )
    (comp (ref "R26")
      (value "22k")
      (footprint "TME:RESISTOR 0805")
      (description "Resistor: thick film; SMD; 0805; 22kΩ; 0,125W; ±1%; -55÷155°C")
      (fields
        (field (name "MANUFACTURER") "YAGEO")
        (field (name "MANUFACTURER PART NUMBER") "RC0805FR-0722KL")
      )
      (libsource (lib "TME") (part "Resistor 22k 0805 1% 0.125W SMD E12"))
    )
    (comp (ref "R27")
      (value "22k")
      (footprint "TME:RESISTOR 0805")
      (description "Resistor: thick film; SMD; 0805; 22kΩ; 0,125W; ±1%; -55÷155°C")
      (fields
        (field (name "MANUFACTURER") "YAGEO")
        (field (name "MANUFACTURER PART NUMBER") "RC0805FR-0722KL")
      )
      (libsource (lib "TME") (part "Resistor 22k 0805 1% 0.125W SMD E12"))
    )
    (comp (ref "R28")
      (value "22k")
      (footprint "TME:RESISTOR 0805")
      (description "Resistor: thick film; SMD; 0805; 22kΩ; 0,125W; ±1%; -55÷155°C")
      (fields
        (field (name "MANUFACTURER") "YAGEO")
        (field (name "MANUFACTURER PART NUMBER") "RC0805FR-0722KL")
      )
      (libsource (lib "TME") (part "Resistor 22k 0805 1% 0.125W SMD E12"))
    )
    (comp (ref "R29")
      (value "22k")
      (footprint "TME:RESISTOR 0805")
      (description "Resistor: thick film; SMD; 0805; 22kΩ; 0,125W; ±1%; -55÷155°C")
      (fields
        (field (name "MANUFACTURER") "YAGEO")
        (field (name "MANUFACTURER PART NUMBER") "RC0805FR-0722KL")
      )
      (libsource (lib "TME") (part "Resistor 22k 0805 1% 0.125W SMD E12"))
    )
    (comp (ref "R30")
      (value "22k")
      (footprint "TME:RESISTOR 0805")
      (description "Resistor: thick film; SMD; 0805; 22kΩ; 0,125W; ±1%; -55÷155°C")
      (fields
        (field (name "MANUFACTURER") "YAGEO")
        (field (name "MANUFACTURER PART NUMBER") "RC0805FR-0722KL")
      )
      (libsource (lib "TME") (part "Resistor 22k 0805 1% 0.125W SMD E12"))
    )
    (comp (ref "R31")
      (value "10k")
      (footprint "TME:RESISTOR 0805")
      (description "Resistor: thick film; SMD; 0805; 10kΩ; 0,125W; ±1%; -55÷155°C")
      (fields
        (field (name "MANUFACTURER") "YAGEO")
        (field (name "MANUFACTURER PART NUMBER") "RC0805FR-0710KL")
      )
      (libsource (lib "TME") (part "Resistor 10k 0805 1% 0.125W SMD E12"))
    )
    (comp (ref "R32")
      (value "3k9")
      (footprint "TME:RESISTOR 0805")
      (description "Resistor: thick film; SMD; 0805; 3.9kΩ; 0,125W; ±1%; -55÷155°C")
      (fields
        (field (name "MANUFACTURER") "YAGEO")
        (field (name "MANUFACTURER PART NUMBER") "RC0805FR-073K9L")
      )
      (libsource (lib "TME") (part "Resistor 3K9 0805 1% 0.125W SMD E12"))
    )
    (comp (ref "R33")
      (value "3k9")
      (footprint "TME:RESISTOR 0805")
      (description "Resistor: thick film; SMD; 0805; 3.9kΩ; 0,125W; ±1%; -55÷155°C")
      (fields
        (field (name "MANUFACTURER") "YAGEO")
        (field (name "MANUFACTURER PART NUMBER") "RC0805FR-073K9L")
      )
      (libsource (lib "TME") (part "Resistor 3K9 0805 1% 0.125W SMD E12"))
    )
    (comp (ref "R34")
      (value "47k")
      (footprint "TME:RESISTOR 0805")
      (description "Resistor: thick film; SMD; 0805; 47kΩ; 0,125W; ±1%; -55÷155°C")
      (fields
        (field (name "MANUFACTURER") "YAGEO")
        (field (name "MANUFACTURER PART NUMBER") "RC0805FR-0747KL")
      )
      (libsource (lib "TME") (part "Resistor 47k 0805 1% 0.125W SMD E12"))
    )
    (comp (ref "R35")
      (value "47k")
      (footprint "TME:RESISTOR 0805")
      (description "Resistor: thick film; SMD; 0805; 47kΩ; 0,125W; ±1%; -55÷155°C")
      (fields
        (field (name "MANUFACTURER") "YAGEO")
        (field (name "MANUFACTURER PART NUMBER") "RC0805FR-0747KL")
      )
      (libsource (lib "TME") (part "Resistor 47k 0805 1% 0.125W SMD E12"))
    )
    (comp (ref "R36")
      (value "10k")
      (footprint "TME:RESISTOR 0805")
      (description "Resistor: thick film; SMD; 0805; 10kΩ; 0,125W; ±1%; -55÷155°C")
      (fields
        (field (name "MANUFACTURER") "YAGEO")
        (field (name "MANUFACTURER PART NUMBER") "RC0805FR-0710KL")
      )
      (libsource (lib "") (part "Resistor 10k 0805 1% 0.125W SMD E12_1"))
    )
    (comp (ref "R37")
      (value "220k")
      (footprint "TME:RESISTOR 0805")
      (description "Resistor: thick film; SMD; 0805; 220kΩ; 0,125W; ±1%; -55÷155°C")
      (fields
        (field (name "MANUFACTURER") "YAGEO")
        (field (name "MANUFACTURER PART NUMBER") "RC0805FR-07220KL")
      )
      (libsource (lib "TME") (part "Resistor 220k 0805 1% 0.125W SMD E12"))
    )
    (comp (ref "R38")
      (value "220k")
      (footprint "TME:RESISTOR 0805")
      (description "Resistor: thick film; SMD; 0805; 220kΩ; 0,125W; ±1%; -55÷155°C")
      (fields
        (field (name "MANUFACTURER") "YAGEO")
        (field (name "MANUFACTURER PART NUMBER") "RC0805FR-07220KL")
      )
      (libsource (lib "TME") (part "Resistor 220k 0805 1% 0.125W SMD E12"))
    )
    (comp (ref "R39")
      (value "680R")
      (footprint "TME:RESISTOR 0805")
      (description "Resistor: thick film; SMD; 0805; 680Ω; 0,125W; ±1%; -55÷155°C")
      (fields
        (field (name "MANUFACTURER") "YAGEO")
        (field (name "MANUFACTURER PART NUMBER") "RC0805FR-07680RL")
      )
      (libsource (lib "TME") (part "Resistor 680R 0805 1% 0.125W SMD E12"))
    )
    (comp (ref "R40")
      (value "100k")
      (footprint "TME:RESISTOR 0805")
      (description "Resistor: thick film; SMD; 0805; 100kΩ; 0,125W; ±1%; -55÷155°C")
      (fields
        (field (name "MANUFACTURER") "YAGEO")
        (field (name "MANUFACTURER PART NUMBER") "RC0805FR-07100KL")
      )
      (libsource (lib "TME") (part "Resistor 100k 0805 1% 0.125W SMD E12"))
    )
    (comp (ref "R41")
      (value "100k")
      (footprint "TME:RESISTOR 0805")
      (description "Resistor: thick film; SMD; 0805; 100kΩ; 0,125W; ±1%; -55÷155°C")
      (fields
        (field (name "MANUFACTURER") "YAGEO")
        (field (name "MANUFACTURER PART NUMBER") "RC0805FR-07100KL")
      )
      (libsource (lib "TME") (part "Resistor 100k 0805 1% 0.125W SMD E12"))
    )
    (comp (ref "R42")
      (value "47k")
      (footprint "TME:RESISTOR 0805")
      (description "Resistor: thick film; SMD; 0805; 47kΩ; 0,125W; ±1%; -55÷155°C")
      (fields
        (field (name "MANUFACTURER") "YAGEO")
        (field (name "MANUFACTURER PART NUMBER") "RC0805FR-0747KL")
      )
      (libsource (lib "TME") (part "Resistor 47k 0805 1% 0.125W SMD E12"))
    )
    (comp (ref "R43")
      (value "10R")
      (footprint "TME:RESISTOR 0805")
      (description "Resistor: thick film; SMD; 0805; 10Ω; 0,125W; ±1%; -55÷155°C")
      (fields
        (field (name "MANUFACTURER") "YAGEO")
        (field (name "MANUFACTURER PART NUMBER") "RC0805FR-0710RL")
      )
      (libsource (lib "TME") (part "Resistor 10R 0805 1% 0.125W SMD E12"))
    )
    (comp (ref "R44")
      (value "100R")
      (footprint "TME:RESISTOR 0805")
      (description "Resistor: thick film; SMD; 0805; 10Ω; 0,125W; ±1%; -55÷155°C")
      (fields
        (field (name "MANUFACTURER") "YAGEO")
        (field (name "MANUFACTURER PART NUMBER") "RC0805FR-07100RL")
      )
      (libsource (lib "TME") (part "Resistor 100R 0805 1% 0.125W SMD E12"))
    )
    (comp (ref "R45")
      (value "100k")
      (footprint "TME:RESISTOR 0805")
      (description "Resistor: thick film; SMD; 0805; 100kΩ; 0,125W; ±1%; -55÷155°C")
      (fields
        (field (name "MANUFACTURER") "YAGEO")
        (field (name "MANUFACTURER PART NUMBER") "RC0805FR-07100KL")
      )
      (libsource (lib "TME") (part "Resistor 100k 0805 1% 0.125W SMD E12"))
    )
    (comp (ref "R46")
      (value "220R")
      (footprint "TME:RESISTOR 0805")
      (description "Resistor: thick film; SMD; 0805; 220Ω; 0,125W; ±1%; -55÷155°C")
      (fields
        (field (name "MANUFACTURER") "YAGEO")
        (field (name "MANUFACTURER PART NUMBER") "RC0805FR-07220RL")
      )
      (libsource (lib "TME") (part "Resistor 220R 0805 1% 0.125W SMD E12"))
    )
    (comp (ref "R47")
      (value "2k7")
      (footprint "TME:RESISTOR 0805")
      (description "Resistor: thick film; SMD; 0805; 2.7kΩ; 0,125W; ±1%; -55÷155°C")
      (fields
        (field (name "MANUFACTURER") "YAGEO")
        (field (name "MANUFACTURER PART NUMBER") "RC0805FR-072K7L")
      )
      (libsource (lib "TME") (part "Resistor 2k7 0805 1% 0.125W SMD E12"))
    )
    (comp (ref "R48")
      (value "220R")
      (footprint "TME:RESISTOR 0805")
      (description "Resistor: thick film; SMD; 0805; 220Ω; 0,125W; ±1%; -55÷155°C")
      (fields
        (field (name "MANUFACTURER") "YAGEO")
        (field (name "MANUFACTURER PART NUMBER") "RC0805FR-07220RL")
      )
      (libsource (lib "TME") (part "Resistor 220R 0805 1% 0.125W SMD E12"))
    )
    (comp (ref "R49")
      (value "100R")
      (footprint "TME:RESISTOR 0805")
      (description "Resistor: thick film; SMD; 0805; 10Ω; 0,125W; ±1%; -55÷155°C")
      (fields
        (field (name "MANUFACTURER") "YAGEO")
        (field (name "MANUFACTURER PART NUMBER") "RC0805FR-07100RL")
      )
      (libsource (lib "TME") (part "Resistor 100R 0805 1% 0.125W SMD E12"))
    )
    (comp (ref "R50")
      (value "22k")
      (footprint "TME:RESISTOR 0805")
      (description "Resistor: thick film; SMD; 0805; 22kΩ; 0,125W; ±1%; -55÷155°C")
      (fields
        (field (name "MANUFACTURER") "YAGEO")
        (field (name "MANUFACTURER PART NUMBER") "RC0805FR-0722KL")
      )
      (libsource (lib "TME") (part "Resistor 22k 0805 1% 0.125W SMD E12"))
    )
    (comp (ref "R51")
      (value "22k")
      (footprint "TME:RESISTOR 0805")
      (description "Resistor: thick film; SMD; 0805; 22kΩ; 0,125W; ±1%; -55÷155°C")
      (fields
        (field (name "MANUFACTURER") "YAGEO")
        (field (name "MANUFACTURER PART NUMBER") "RC0805FR-0722KL")
      )
      (libsource (lib "TME") (part "Resistor 22k 0805 1% 0.125W SMD E12"))
    )
    (comp (ref "R52")
      (value "22k")
      (footprint "TME:RESISTOR 0805")
      (description "Resistor: thick film; SMD; 0805; 22kΩ; 0,125W; ±1%; -55÷155°C")
      (fields
        (field (name "MANUFACTURER") "YAGEO")
        (field (name "MANUFACTURER PART NUMBER") "RC0805FR-0722KL")
      )
      (libsource (lib "TME") (part "Resistor 22k 0805 1% 0.125W SMD E12"))
    )
    (comp (ref "T1")
      (value "BC847B")
      (footprint "TME:SOT23-3")
      (description "Transistor: NPN; bipolar; 50V; 0.1A; 0.225W; SOT23")
      (fields (field (name "MANUFACTURER") "ONSEMI") (field (name "MANUFACTURER PART NUMBER") "BC847BLT1G"))
      (libsource (lib "TME") (part "Transistor NPN 100mA 50V 0.225W BC847BLT1G"))
    )
    (comp (ref "T2")
      (value "BC847B")
      (footprint "TME:SOT23-3")
      (description "Transistor: NPN; bipolar; 50V; 0.1A; 0.225W; SOT23")
      (fields (field (name "MANUFACTURER") "ONSEMI") (field (name "MANUFACTURER PART NUMBER") "BC847BLT1G"))
      (libsource (lib "TME") (part "Transistor NPN 100mA 50V 0.225W BC847BLT1G"))
    )
    (comp (ref "T3")
      (value "BC847B")
      (footprint "TME:SOT23-3")
      (description "Transistor: NPN; bipolar; 50V; 0.1A; 0.225W; SOT23")
      (fields (field (name "MANUFACTURER") "ONSEMI") (field (name "MANUFACTURER PART NUMBER") "BC847BLT1G"))
      (libsource (lib "TME") (part "Transistor NPN 100mA 50V 0.225W BC847BLT1G"))
    )
    (comp (ref "U1")
      (value "LM833")
      (footprint "TME:SOIC-8")
      (description "Audio Amplifiers SOIC8 5-36V 15MHz LM833")
      (fields
        (field (name "MANUFACTURER") "STMicroelectronics")
        (field (name "MANUFACTURER PART NUMBER") "LM833DT")
      )
      (libsource (lib "TME") (part "IC Op-Amp Dual LM833DT SOIC-8"))
    )
    (comp (ref "U2")
      (value "40106B")
      (footprint "TME:SOIC-14")
      (description "IC: digital; NOT; Ch: 6; IN: 1; CMOS; SMD; SOIC14; 3÷18VDC; -55÷125°C")
      (fields
        (field (name "MANUFACTURER") "TEXAS INSTRUMENTS")
        (field (name "MANUFACTURER PART NUMBER") "LM833DT")
      )
      (libsource (lib "TME") (part "IC Gate NOT Schmitt 6CH SOIC14"))
    )
    (comp (ref "U3")
      (value "SN74LVC1G3157")
      (footprint "TME:SOT23-6")
      (description "IC: analog switch; SPDT; Ch: 1; SOT23-6; 1.65÷5.5VDC")
      (fields
        (field (name "MANUFACTURER") "TEXAS INSTRUMENTS")
        (field (name "MANUFACTURER PART NUMBER") "SN74LVC1G3157DBVR")
      )
      (libsource (lib "TME") (part "IC SPDT Analog Switch SOT-23-6 SN74LVC1G3157DBVR"))
    )
    (comp (ref "U4")
      (value "SN74LVC1G3157")
      (footprint "TME:SOT23-6")
      (description "IC: analog switch; SPDT; Ch: 1; SOT23-6; 1.65÷5.5VDC")
      (fields
        (field (name "MANUFACTURER") "TEXAS INSTRUMENTS")
        (field (name "MANUFACTURER PART NUMBER") "SN74LVC1G3157DBVR")
      )
      (libsource (lib "") (part "IC SPDT Analog Switch SOT-23-6 SN74LVC1G3157DBVR_1"))
    )
    (comp (ref "U5")
      (value "1117")
      (footprint "TME:SOT223")
      (description "IC: voltage regulator; LDO,linear,adjustable; 1.25÷13.65V; 1A")
      (fields
        (field (name "MANUFACTURER") "DIOTEC SEMICONDUCTOR")
        (field (name "MANUFACTURER PART NUMBER") "LDI1117-ADH")
      )
      (libsource (lib "TME") (part "IC LDO ADJ 1A SOT223 SMD LDI1117"))
    )
    (comp (ref "U6")
      (value "L78L05")
      (footprint "TME:SOIC-8")
      (description "IC: voltage regulator; linear,fixed; 5V; 0.1A; SO8; SMD; reel,tape")
      (fields
        (field (name "MANUFACTURER") "STMicroelectronics")
        (field (name "MANUFACTURER PART NUMBER") "L78L05CD13TR")
      )
      (libsource (lib "TME") (part "IC LDO 5V 0.1A SO8 SMD L78L05CD13TR"))
    )
    (comp (ref "V1")
      (value "12AX7")
      (footprint "TME:TUbe 9pin NOVAL")
      (libsource (lib "") (part "Tube 12AX7 / ECC83 9pin NOVAL_1"))
    )
  )
  (nets
    (net (code "1") (name "+4V5") (class "Default")
      (node (ref "C23") (pin "2") (pinfunction "2_2") (pintype "passive"))
      (node (ref "R1") (pin "2") (pinfunction "2_2") (pintype "passive"))
      (node (ref "R27") (pin "1") (pinfunction "1_1") (pintype "passive"))
      (node (ref "R30") (pin "2") (pinfunction "2_2") (pintype "passive"))
      (node (ref "R49") (pin "1") (pinfunction "1_1") (pintype "passive"))
    )
    (net (code "2") (name "+5V") (class "Default")
      (node (ref "C20") (pin "2") (pinfunction "2_2") (pintype "passive"))
      (node (ref "C21") (pin "2") (pinfunction "2_2") (pintype "passive"))
      (node (ref "C36") (pin "2") (pinfunction "2_2") (pintype "passive"))
      (node (ref "R32") (pin "2") (pinfunction "2_2") (pintype "passive"))
      (node (ref "R33") (pin "2") (pinfunction "2_2") (pintype "passive"))
      (node (ref "R45") (pin "2") (pinfunction "2_2") (pintype "passive"))
      (node (ref "U3") (pin "5") (pinfunction "VCC_5") (pintype "power_in"))
      (node (ref "U4") (pin "5") (pinfunction "VCC_5") (pintype "power_in"))
      (node (ref "U6") (pin "1") (pinfunction "VOUT_1") (pintype "passive"))
    )
    (net (code "3") (name "+6V3") (class "Default")
      (node (ref "C38") (pin "2") (pinfunction "2_2") (pintype "passive"))
      (node (ref "J11") (pin "1") (pinfunction "1_1") (pintype "passive"))
      (node (ref "J13") (pin "1") (pinfunction "1_1") (pintype "passive"))
      (node (ref "R43") (pin "2") (pinfunction "2_2") (pintype "passive"))
      (node (ref "U5") (pin "2") (pinfunction "VOUT_2") (pintype "passive"))
      (node (ref "U5") (pin "4") (pinfunction "VOUT_4") (pintype "passive"))
    )
    (net (code "4") (name "+9V") (class "Default")
      (node (ref "C19") (pin "2") (pinfunction "2_2") (pintype "passive"))
      (node (ref "C22") (pin "2") (pinfunction "2_2") (pintype "passive"))
      (node (ref "C24") (pin "2") (pinfunction "2_2") (pintype "passive"))
      (node (ref "C35") (pin "2") (pinfunction "2_2") (pintype "passive"))
      (node (ref "D1") (pin "2") (pinfunction "2_2") (pintype "passive"))
      (node (ref "D2") (pin "1") (pinfunction "1_1") (pintype "passive"))
      (node (ref "J10") (pin "1") (pinfunction "1_1") (pintype "passive"))
      (node (ref "J9") (pin "1") (pinfunction "1_1") (pintype "passive"))
      (node (ref "R25") (pin "2") (pinfunction "2_2") (pintype "passive"))
      (node (ref "R26") (pin "2") (pinfunction "2_2") (pintype "passive"))
      (node (ref "R27") (pin "2") (pinfunction "2_2") (pintype "passive"))
      (node (ref "R28") (pin "2") (pinfunction "2_2") (pintype "passive"))
      (node (ref "R51") (pin "2") (pinfunction "2_2") (pintype "passive"))
      (node (ref "U1") (pin "8") (pinfunction "V+_8") (pintype "passive"))
      (node (ref "U2") (pin "14") (pinfunction "V+_14") (pintype "passive"))
      (node (ref "U5") (pin "3") (pinfunction "VIN_3") (pintype "passive"))
      (node (ref "U6") (pin "8") (pinfunction "VIN_8") (pintype "passive"))
    )
    (net (code "5") (name "+HV") (class "Default")
      (node (ref "C31") (pin "2") (pinfunction "2_2") (pintype "passive"))
      (node (ref "D8") (pin "2") (pinfunction "2_2") (pintype "passive"))
      (node (ref "R4") (pin "2") (pinfunction "2_2") (pintype "passive"))
      (node (ref "R6") (pin "2") (pinfunction "2_2") (pintype "passive"))
    )
    (net (code "6") (name "/EFFECT_INPUT") (class "Default")
      (node (ref "R15") (pin "1") (pinfunction "1_1") (pintype "passive"))
      (node (ref "R26") (pin "1") (pinfunction "1_1") (pintype "passive"))
      (node (ref "R50") (pin "2") (pinfunction "2_2") (pintype "passive"))
      (node (ref "U3") (pin "3") (pinfunction "B1_3") (pintype "passive"))
    )
    (net (code "7") (name "/EFFECT_OUTPUT") (class "Default")
      (node (ref "R23") (pin "2") (pinfunction "2_2") (pintype "passive"))
      (node (ref "U4") (pin "3") (pinfunction "B1_3") (pintype "passive"))
    )
    (net (code "8") (name "/INPUT_BUFFER") (class "Default")
      (node (ref "C16") (pin "1") (pinfunction "1_1") (pintype "passive"))
      (node (ref "U1") (pin "1") (pinfunction "OUT_1") (pintype "passive"))
      (node (ref "U1") (pin "2") (pinfunction "IN-_2") (pintype "passive"))
    )
    (net (code "9") (name "/OUTPUT_BUFFER") (class "Default")
      (node (ref "C17") (pin "2") (pinfunction "2_2") (pintype "passive"))
      (node (ref "J1") (pin "3") (pinfunction "T_3") (pintype "passive"))
    )
    (net (code "10") (name "/SET") (class "Default")
      (node (ref "R31") (pin "2") (pinfunction "2_2") (pintype "passive"))
      (node (ref "R36") (pin "2") (pinfunction "2_2") (pintype "passive"))
      (node (ref "R42") (pin "1") (pinfunction "1_1") (pintype "passive"))
      (node (ref "U3") (pin "6") (pinfunction "S_6") (pintype "passive"))
      (node (ref "U4") (pin "6") (pinfunction "S_6") (pintype "passive"))
    )
    (net (code "11") (name "GND") (class "Default")
      (node (ref "C11") (pin "1") (pinfunction "1_1") (pintype "passive"))
      (node (ref "C12") (pin "1") (pinfunction "1_1") (pintype "passive"))
      (node (ref "C13") (pin "1") (pinfunction "1_1") (pintype "passive"))
      (node (ref "C14") (pin "1") (pinfunction "1_1") (pintype "passive"))
      (node (ref "C15") (pin "1") (pinfunction "1_1") (pintype "passive"))
      (node (ref "C19") (pin "1") (pinfunction "1_1") (pintype "passive"))
      (node (ref "C2") (pin "1") (pinfunction "1_1") (pintype "passive"))
      (node (ref "C20") (pin "1") (pinfunction "1_1") (pintype "passive"))
      (node (ref "C21") (pin "1") (pinfunction "1_1") (pintype "passive"))
      (node (ref "C22") (pin "1") (pinfunction "1_1") (pintype "passive"))
      (node (ref "C23") (pin "1") (pinfunction "1_1") (pintype "passive"))
      (node (ref "C24") (pin "1") (pinfunction "1_1") (pintype "passive"))
      (node (ref "C31") (pin "1") (pinfunction "1_1") (pintype "passive"))
      (node (ref "C34") (pin "1") (pinfunction "1_1") (pintype "passive"))
      (node (ref "C35") (pin "1") (pinfunction "1_1") (pintype "passive"))
      (node (ref "C36") (pin "1") (pinfunction "1_1") (pintype "passive"))
      (node (ref "C37") (pin "1") (pinfunction "1_1") (pintype "passive"))
      (node (ref "C38") (pin "1") (pinfunction "1_1") (pintype "passive"))
      (node (ref "C4") (pin "1") (pinfunction "1_1") (pintype "passive"))
      (node (ref "D1") (pin "1") (pinfunction "1_1") (pintype "passive"))
      (node (ref "J1") (pin "1") (pinfunction "S_1") (pintype "passive"))
      (node (ref "J12") (pin "1") (pinfunction "1_1") (pintype "passive"))
      (node (ref "J2") (pin "1") (pinfunction "S_1") (pintype "passive"))
      (node (ref "J25") (pin "2") (pinfunction "2_2") (pintype "passive"))
      (node (ref "J9") (pin "2") (pinfunction "2_2") (pintype "passive"))
      (node (ref "R13") (pin "1") (pinfunction "1_1") (pintype "passive"))
      (node (ref "R19") (pin "1") (pinfunction "1_1") (pintype "passive"))
      (node (ref "R20") (pin "1") (pinfunction "1_1") (pintype "passive"))
      (node (ref "R21") (pin "3") (pinfunction "3_3") (pintype "passive"))
      (node (ref "R22") (pin "1") (pinfunction "1_1") (pintype "passive"))
      (node (ref "R23") (pin "1") (pinfunction "1_1") (pintype "passive"))
      (node (ref "R24") (pin "1") (pinfunction "1_1") (pintype "passive"))
      (node (ref "R29") (pin "1") (pinfunction "1_1") (pintype "passive"))
      (node (ref "R3") (pin "2") (pinfunction "2_2") (pintype "passive"))
      (node (ref "R30") (pin "1") (pinfunction "1_1") (pintype "passive"))
      (node (ref "R40") (pin "1") (pinfunction "1_1") (pintype "passive"))
      (node (ref "R41") (pin "1") (pinfunction "1_1") (pintype "passive"))
      (node (ref "R48") (pin "1") (pinfunction "1_1") (pintype "passive"))
      (node (ref "R50") (pin "1") (pinfunction "1_1") (pintype "passive"))
      (node (ref "R52") (pin "1") (pinfunction "1_1") (pintype "passive"))
      (node (ref "T1") (pin "2") (pinfunction "E_2") (pintype "passive"))
      (node (ref "T2") (pin "2") (pinfunction "E_2") (pintype "passive"))
      (node (ref "T3") (pin "2") (pinfunction "E_2") (pintype "passive"))
      (node (ref "U1") (pin "4") (pinfunction "V-_4") (pintype "passive"))
      (node (ref "U2") (pin "7") (pinfunction "V-_7") (pintype "passive"))
      (node (ref "U3") (pin "2") (pinfunction "GND_2") (pintype "power_in"))
      (node (ref "U4") (pin "2") (pinfunction "GND_2") (pintype "power_in"))
      (node (ref "U6") (pin "2") (pinfunction "GND_2") (pintype "passive"))
      (node (ref "U6") (pin "3") (pinfunction "GND_3") (pintype "passive"))
      (node (ref "U6") (pin "6") (pinfunction "GND_6") (pintype "passive"))
      (node (ref "U6") (pin "7") (pinfunction "GND_7") (pintype "passive"))
    )
    (net (code "12") (name "Net-(C1-Pad1)") (class "Default")
      (node (ref "C1") (pin "1") (pinfunction "1_1") (pintype "passive"))
      (node (ref "C2") (pin "2") (pinfunction "2_2") (pintype "passive"))
      (node (ref "R2") (pin "2") (pinfunction "2_2") (pintype "passive"))
      (node (ref "R3") (pin "1") (pinfunction "1_1") (pintype "passive"))
    )
    (net (code "13") (name "Net-(C3-Pad2)") (class "Default")
      (node (ref "C3") (pin "2") (pinfunction "2_2") (pintype "passive"))
      (node (ref "C7") (pin "2") (pinfunction "2_2") (pintype "passive"))
      (node (ref "R10") (pin "2") (pinfunction "2_2") (pintype "passive"))
    )
    (net (code "14") (name "Net-(C6-Pad1)") (class "Default")
      (node (ref "C6") (pin "1") (pinfunction "1_1") (pintype "passive"))
      (node (ref "R12") (pin "2") (pinfunction "2_2") (pintype "passive"))
    )
    (net (code "15") (name "Net-(C6-Pad2)") (class "Default")
      (node (ref "C6") (pin "2") (pinfunction "2_2") (pintype "passive"))
      (node (ref "J4") (pin "1") (pinfunction "1_1") (pintype "passive"))
      (node (ref "R13") (pin "2") (pinfunction "2_2") (pintype "passive"))
    )
    (net (code "16") (name "Net-(C7-Pad1)") (class "Default")
      (node (ref "C7") (pin "1") (pinfunction "1_1") (pintype "passive"))
      (node (ref "R17") (pin "3") (pinfunction "3_3") (pintype "passive"))
    )
    (net (code "17") (name "Net-(C8-Pad2)") (class "Default")
      (node (ref "C8") (pin "2") (pinfunction "2_2") (pintype "passive"))
      (node (ref "R10") (pin "1") (pinfunction "1_1") (pintype "passive"))
      (node (ref "R14") (pin "3") (pinfunction "3_3") (pintype "passive"))
    )
    (net (code "18") (name "Net-(C9-Pad2)") (class "Default")
      (node (ref "C9") (pin "2") (pinfunction "2_2") (pintype "passive"))
      (node (ref "R18") (pin "1") (pinfunction "1_1") (pintype "passive"))
    )
    (net (code "19") (name "Net-(C10-Pad1)") (class "Default")
      (node (ref "C10") (pin "1") (pinfunction "1_1") (pintype "passive"))
      (node (ref "R14") (pin "1") (pinfunction "1_1") (pintype "passive"))
      (node (ref "R20") (pin "2") (pinfunction "2_2") (pintype "passive"))
    )
    (net (code "20") (name "Net-(C10-Pad2)") (class "Default")
      (node (ref "C10") (pin "2") (pinfunction "2_2") (pintype "passive"))
      (node (ref "C8") (pin "1") (pinfunction "1_1") (pintype "passive"))
      (node (ref "R14") (pin "2") (pinfunction "2_2") (pintype "passive"))
      (node (ref "R16") (pin "1") (pinfunction "1_1") (pintype "passive"))
    )
    (net (code "21") (name "Net-(C11-Pad2)") (class "Default")
      (node (ref "C11") (pin "2") (pinfunction "2_2") (pintype "passive"))
      (node (ref "R17") (pin "1") (pinfunction "1_1") (pintype "passive"))
    )
    (net (code "22") (name "Net-(C12-Pad2)") (class "Default")
      (node (ref "C12") (pin "2") (pinfunction "2_2") (pintype "passive"))
      (node (ref "C3") (pin "1") (pinfunction "1_1") (pintype "passive"))
      (node (ref "C4") (pin "2") (pinfunction "2_2") (pintype "passive"))
      (node (ref "R7") (pin "2") (pinfunction "2_2") (pintype "passive"))
    )
    (net (code "23") (name "Net-(C13-Pad2)") (class "Default")
      (node (ref "C13") (pin "2") (pinfunction "2_2") (pintype "passive"))
      (node (ref "C14") (pin "2") (pinfunction "2_2") (pintype "passive"))
      (node (ref "C15") (pin "2") (pinfunction "2_2") (pintype "passive"))
      (node (ref "J6") (pin "1") (pinfunction "1_1") (pintype "passive"))
      (node (ref "J8") (pin "1") (pinfunction "1_1") (pintype "passive"))
      (node (ref "R21") (pin "1") (pinfunction "1_1") (pintype "passive"))
      (node (ref "R21") (pin "2") (pinfunction "2_2") (pintype "passive"))
      (node (ref "R22") (pin "2") (pinfunction "2_2") (pintype "passive"))
    )
    (net (code "24") (name "Net-(C18-Pad1)") (class "Default")
      (node (ref "C18") (pin "1") (pinfunction "1_1") (pintype "passive"))
      (node (ref "R23") (pin "3") (pinfunction "3_3") (pintype "passive"))
    )
    (net (code "25") (name "Net-(C18-Pad2)") (class "Default")
      (node (ref "C18") (pin "2") (pinfunction "2_2") (pintype "passive"))
      (node (ref "R16") (pin "2") (pinfunction "2_2") (pintype "passive"))
      (node (ref "R17") (pin "2") (pinfunction "2_2") (pintype "passive"))
    )
    (net (code "26") (name "Net-(C25-Pad2)") (class "Default")
      (node (ref "C25") (pin "2") (pinfunction "2_2") (pintype "passive"))
      (node (ref "D2") (pin "2") (pinfunction "2_2") (pintype "passive"))
      (node (ref "D3") (pin "1") (pinfunction "1_1") (pintype "passive"))
    )
    (net (code "27") (name "Net-(C26-Pad2)") (class "Default")
      (node (ref "C26") (pin "2") (pinfunction "2_2") (pintype "passive"))
      (node (ref "D3") (pin "2") (pinfunction "2_2") (pintype "passive"))
      (node (ref "D4") (pin "1") (pinfunction "1_1") (pintype "passive"))
    )
    (net (code "28") (name "Net-(C27-Pad2)") (class "Default")
      (node (ref "C27") (pin "2") (pinfunction "2_2") (pintype "passive"))
      (node (ref "D4") (pin "2") (pinfunction "2_2") (pintype "passive"))
      (node (ref "D5") (pin "1") (pinfunction "1_1") (pintype "passive"))
    )
    (net (code "29") (name "Net-(C28-Pad2)") (class "Default")
      (node (ref "C28") (pin "2") (pinfunction "2_2") (pintype "passive"))
      (node (ref "D5") (pin "2") (pinfunction "2_2") (pintype "passive"))
      (node (ref "D6") (pin "1") (pinfunction "1_1") (pintype "passive"))
    )
    (net (code "30") (name "Net-(C29-Pad2)") (class "Default")
      (node (ref "C29") (pin "2") (pinfunction "2_2") (pintype "passive"))
      (node (ref "D6") (pin "2") (pinfunction "2_2") (pintype "passive"))
      (node (ref "D7") (pin "1") (pinfunction "1_1") (pintype "passive"))
    )
    (net (code "31") (name "Net-(C30-Pad2)") (class "Default")
      (node (ref "C30") (pin "2") (pinfunction "2_2") (pintype "passive"))
      (node (ref "D7") (pin "2") (pinfunction "2_2") (pintype "passive"))
      (node (ref "D8") (pin "1") (pinfunction "1_1") (pintype "passive"))
    )
    (net (code "32") (name "Net-(C32-Pad1)") (class "Default")
      (node (ref "C32") (pin "1") (pinfunction "1_1") (pintype "passive"))
      (node (ref "D9") (pin "2") (pinfunction "2_2") (pintype "passive"))
      (node (ref "R37") (pin "1") (pinfunction "1_1") (pintype "passive"))
    )
    (net (code "33") (name "Net-(C32-Pad2)") (class "Default")
      (node (ref "C32") (pin "2") (pinfunction "2_2") (pintype "passive"))
      (node (ref "C33") (pin "1") (pinfunction "1_1") (pintype "passive"))
      (node (ref "C37") (pin "2") (pinfunction "2_2") (pintype "passive"))
      (node (ref "J25") (pin "1") (pinfunction "1_1") (pintype "passive"))
      (node (ref "R45") (pin "1") (pinfunction "1_1") (pintype "passive"))
    )
    (net (code "34") (name "Net-(C33-Pad2)") (class "Default")
      (node (ref "C33") (pin "2") (pinfunction "2_2") (pintype "passive"))
      (node (ref "D10") (pin "2") (pinfunction "2_2") (pintype "passive"))
      (node (ref "R38") (pin "1") (pinfunction "1_1") (pintype "passive"))
    )
    (net (code "35") (name "Net-(J2-T)") (class "Default")
      (node (ref "J2") (pin "3") (pinfunction "T_3") (pintype "passive"))
      (node (ref "R2") (pin "1") (pinfunction "1_1") (pintype "passive"))
    )
    (net (code "36") (name "Net-(J3-Pad1)") (class "Default")
      (node (ref "J3") (pin "1") (pinfunction "1_1") (pintype "passive"))
      (node (ref "R5") (pin "1") (pinfunction "1_1") (pintype "passive"))
      (node (ref "R7") (pin "1") (pinfunction "1_1") (pintype "passive"))
    )
    (net (code "37") (name "Net-(J5-Pad1)") (class "Default")
      (node (ref "J5") (pin "1") (pinfunction "1_1") (pintype "passive"))
      (node (ref "R11") (pin "1") (pinfunction "1_1") (pintype "passive"))
      (node (ref "R9") (pin "1") (pinfunction "1_1") (pintype "passive"))
    )
    (net (code "38") (name "Net-(J7-Pad1)") (class "Default")
      (node (ref "J7") (pin "1") (pinfunction "1_1") (pintype "passive"))
      (node (ref "R18") (pin "2") (pinfunction "2_2") (pintype "passive"))
      (node (ref "R19") (pin "2") (pinfunction "2_2") (pintype "passive"))
    )
    (net (code "39") (name "Net-(J10-Pad2)") (class "Default")
      (node (ref "J10") (pin "2") (pinfunction "2_2") (pintype "passive"))
      (node (ref "R39") (pin "2") (pinfunction "2_2") (pintype "passive"))
    )
    (net (code "40") (name "Net-(J23-Pad1)") (class "Default")
      (node (ref "J23") (pin "1") (pinfunction "1_1") (pintype "passive"))
      (node (ref "J24") (pin "1") (pinfunction "1_1") (pintype "passive"))
    )
    (net (code "41") (name "Net-(J23-Pad2)") (class "Default")
      (node (ref "J23") (pin "2") (pinfunction "2_2") (pintype "passive"))
      (node (ref "J24") (pin "2") (pinfunction "2_2") (pintype "passive"))
    )
    (net (code "42") (name "Net-(R4-Pad1)") (class "Default")
      (node (ref "R4") (pin "1") (pinfunction "1_1") (pintype "passive"))
      (node (ref "R5") (pin "2") (pinfunction "2_2") (pintype "passive"))
    )
    (net (code "43") (name "Net-(R6-Pad1)") (class "Default")
      (node (ref "R6") (pin "1") (pinfunction "1_1") (pintype "passive"))
      (node (ref "R9") (pin "2") (pinfunction "2_2") (pintype "passive"))
    )
    (net (code "44") (name "Net-(R11-Pad2)") (class "Default")
      (node (ref "R11") (pin "2") (pinfunction "2_2") (pintype "passive"))
      (node (ref "R12") (pin "1") (pinfunction "1_1") (pintype "passive"))
    )
    (net (code "45") (name "Net-(R43-Pad1)") (class "Default")
      (node (ref "R43") (pin "1") (pinfunction "1_1") (pintype "passive"))
      (node (ref "R44") (pin "2") (pinfunction "2_2") (pintype "passive"))
    )
    (net (code "46") (name "Net-(R46-Pad1)") (class "Default")
      (node (ref "R46") (pin "1") (pinfunction "1_1") (pintype "passive"))
      (node (ref "R48") (pin "2") (pinfunction "2_2") (pintype "passive"))
    )
    (net (code "47") (name "Net-(T1-B)") (class "Default")
      (node (ref "D9") (pin "1") (pinfunction "1_1") (pintype "passive"))
      (node (ref "R35") (pin "1") (pinfunction "1_1") (pintype "passive"))
      (node (ref "R40") (pin "2") (pinfunction "2_2") (pintype "passive"))
      (node (ref "T1") (pin "1") (pinfunction "B_1") (pintype "passive"))
    )
    (net (code "48") (name "Net-(T1-C)") (class "Default")
      (node (ref "R31") (pin "1") (pinfunction "1_1") (pintype "passive"))
      (node (ref "R32") (pin "1") (pinfunction "1_1") (pintype "passive"))
      (node (ref "R34") (pin "1") (pinfunction "1_1") (pintype "passive"))
      (node (ref "R37") (pin "2") (pinfunction "2_2") (pintype "passive"))
      (node (ref "T1") (pin "3") (pinfunction "C_3") (pintype "passive"))
    )
    (net (code "49") (name "Net-(T2-B)") (class "Default")
      (node (ref "D10") (pin "1") (pinfunction "1_1") (pintype "passive"))
      (node (ref "R34") (pin "2") (pinfunction "2_2") (pintype "passive"))
      (node (ref "R41") (pin "2") (pinfunction "2_2") (pintype "passive"))
      (node (ref "T2") (pin "1") (pinfunction "B_1") (pintype "passive"))
    )
    (net (code "50") (name "Net-(T2-C)") (class "Default")
      (node (ref "R33") (pin "1") (pinfunction "1_1") (pintype "passive"))
      (node (ref "R35") (pin "2") (pinfunction "2_2") (pintype "passive"))
      (node (ref "R36") (pin "1") (pinfunction "1_1") (pintype "passive"))
      (node (ref "R38") (pin "2") (pinfunction "2_2") (pintype "passive"))
      (node (ref "T2") (pin "3") (pinfunction "C_3") (pintype "passive"))
    )
    (net (code "51") (name "Net-(T3-B)") (class "Default")
      (node (ref "R42") (pin "2") (pinfunction "2_2") (pintype "passive"))
      (node (ref "T3") (pin "1") (pinfunction "B_1") (pintype "passive"))
    )
    (net (code "52") (name "Net-(T3-C)") (class "Default")
      (node (ref "R39") (pin "1") (pinfunction "1_1") (pintype "passive"))
      (node (ref "T3") (pin "3") (pinfunction "C_3") (pintype "passive"))
    )
    (net (code "53") (name "Net-(U1A-IN+)") (class "Default")
      (node (ref "C1") (pin "2") (pinfunction "2_2") (pintype "passive"))
      (node (ref "R1") (pin "1") (pinfunction "1_1") (pintype "passive"))
      (node (ref "U1") (pin "3") (pinfunction "IN+_3") (pintype "passive"))
    )
    (net (code "54") (name "Net-(U1B-IN+)") (class "Default")
      (node (ref "R49") (pin "2") (pinfunction "2_2") (pintype "passive"))
      (node (ref "U1") (pin "5") (pinfunction "IN+_5") (pintype "passive"))
    )
    (net (code "55") (name "Net-(U1B-IN-)") (class "Default")
      (node (ref "C5") (pin "2") (pinfunction "2_2") (pintype "passive"))
      (node (ref "R15") (pin "2") (pinfunction "2_2") (pintype "passive"))
      (node (ref "R8") (pin "1") (pinfunction "1_1") (pintype "passive"))
      (node (ref "U1") (pin "6") (pinfunction "IN-_6") (pintype "passive"))
    )
    (net (code "56") (name "Net-(U1B-OUT)") (class "Default")
      (node (ref "C5") (pin "1") (pinfunction "1_1") (pintype "passive"))
      (node (ref "C9") (pin "1") (pinfunction "1_1") (pintype "passive"))
      (node (ref "R8") (pin "2") (pinfunction "2_2") (pintype "passive"))
      (node (ref "R8") (pin "3") (pinfunction "3_3") (pintype "passive"))
      (node (ref "U1") (pin "7") (pinfunction "OUT_7") (pintype "passive"))
    )
    (net (code "57") (name "Net-(U2A-A)") (class "Default")
      (node (ref "C34") (pin "2") (pinfunction "2_2") (pintype "passive"))
      (node (ref "R47") (pin "1") (pinfunction "1_1") (pintype "passive"))
      (node (ref "U2") (pin "1") (pinfunction "A_1") (pintype "passive"))
    )
    (net (code "58") (name "Net-(U2A-~{A})") (class "Default")
      (node (ref "C25") (pin "1") (pinfunction "1_1") (pintype "passive"))
      (node (ref "R47") (pin "2") (pinfunction "2_2") (pintype "passive"))
      (node (ref "U2") (pin "2") (pinfunction "~{A}_2") (pintype "passive"))
      (node (ref "U2") (pin "3") (pinfunction "B_3") (pintype "passive"))
    )
    (net (code "59") (name "Net-(U2B-~{B})") (class "Default")
      (node (ref "C26") (pin "1") (pinfunction "1_1") (pintype "passive"))
      (node (ref "U2") (pin "4") (pinfunction "~{B}_4") (pintype "passive"))
      (node (ref "U2") (pin "5") (pinfunction "C_5") (pintype "passive"))
    )
    (net (code "60") (name "Net-(U2C-~{C})") (class "Default")
      (node (ref "C27") (pin "1") (pinfunction "1_1") (pintype "passive"))
      (node (ref "U2") (pin "6") (pinfunction "~{C}_6") (pintype "passive"))
      (node (ref "U2") (pin "9") (pinfunction "D_9") (pintype "passive"))
    )
    (net (code "61") (name "Net-(U2D-~{D})") (class "Default")
      (node (ref "C28") (pin "1") (pinfunction "1_1") (pintype "passive"))
      (node (ref "U2") (pin "11") (pinfunction "E_11") (pintype "passive"))
      (node (ref "U2") (pin "8") (pinfunction "~{D}_8") (pintype "passive"))
    )
    (net (code "62") (name "Net-(U2E-~{E})") (class "Default")
      (node (ref "C29") (pin "1") (pinfunction "1_1") (pintype "passive"))
      (node (ref "U2") (pin "10") (pinfunction "~{E}_10") (pintype "passive"))
      (node (ref "U2") (pin "13") (pinfunction "F_13") (pintype "passive"))
    )
    (net (code "63") (name "Net-(U2F-~{F})") (class "Default")
      (node (ref "C30") (pin "1") (pinfunction "1_1") (pintype "passive"))
      (node (ref "U2") (pin "12") (pinfunction "~{F}_12") (pintype "passive"))
    )
    (net (code "64") (name "Net-(U3-A)") (class "Default")
      (node (ref "C16") (pin "2") (pinfunction "2_2") (pintype "passive"))
      (node (ref "R24") (pin "2") (pinfunction "2_2") (pintype "passive"))
      (node (ref "R28") (pin "1") (pinfunction "1_1") (pintype "passive"))
      (node (ref "U3") (pin "4") (pinfunction "A_4") (pintype "passive"))
    )
    (net (code "65") (name "Net-(U3-B2)") (class "Default")
      (node (ref "R51") (pin "1") (pinfunction "1_1") (pintype "passive"))
      (node (ref "R52") (pin "2") (pinfunction "2_2") (pintype "passive"))
      (node (ref "U3") (pin "1") (pinfunction "B2_1") (pintype "passive"))
      (node (ref "U4") (pin "1") (pinfunction "B2_1") (pintype "passive"))
    )
    (net (code "66") (name "Net-(U4-A)") (class "Default")
      (node (ref "C17") (pin "1") (pinfunction "1_1") (pintype "passive"))
      (node (ref "R25") (pin "1") (pinfunction "1_1") (pintype "passive"))
      (node (ref "R29") (pin "2") (pinfunction "2_2") (pintype "passive"))
      (node (ref "U4") (pin "4") (pinfunction "A_4") (pintype "passive"))
    )
    (net (code "67") (name "Net-(U5-ADJ{slash}GND)") (class "Default")
      (node (ref "R44") (pin "1") (pinfunction "1_1") (pintype "passive"))
      (node (ref "R46") (pin "2") (pinfunction "2_2") (pintype "passive"))
      (node (ref "U5") (pin "1") (pinfunction "ADJ/GND_1") (pintype "passive"))
    )
    (net (code "68") (name "Net-(V1A-CATHODE2)") (class "Default")
      (node (ref "J21") (pin "1") (pinfunction "1_1") (pintype "passive"))
      (node (ref "V1") (pin "3") (pinfunction "CATHODE2_3") (pintype "passive"))
    )
    (net (code "69") (name "Net-(V1A-GRID2)") (class "Default")
      (node (ref "J17") (pin "1") (pinfunction "1_1") (pintype "passive"))
      (node (ref "V1") (pin "2") (pinfunction "GRID2_2") (pintype "passive"))
    )
    (net (code "70") (name "Net-(V1A-PLATE2)") (class "Default")
      (node (ref "J14") (pin "1") (pinfunction "1_1") (pintype "passive"))
      (node (ref "V1") (pin "1") (pinfunction "PLATE2_1") (pintype "passive"))
    )
    (net (code "71") (name "Net-(V1B-CATHODE1)") (class "Default")
      (node (ref "J22") (pin "1") (pinfunction "1_1") (pintype "passive"))
      (node (ref "V1") (pin "8") (pinfunction "CATHODE1_8") (pintype "passive"))
    )
    (net (code "72") (name "Net-(V1B-GRID1)") (class "Default")
      (node (ref "J18") (pin "1") (pinfunction "1_1") (pintype "passive"))
      (node (ref "V1") (pin "7") (pinfunction "GRID1_7") (pintype "passive"))
    )
    (net (code "73") (name "Net-(V1B-PLATE1)") (class "Default")
      (node (ref "J15") (pin "1") (pinfunction "1_1") (pintype "passive"))
      (node (ref "V1") (pin "6") (pinfunction "PLATE1_6") (pintype "passive"))
    )
    (net (code "74") (name "Net-(V1C-FIL1)") (class "Default")
      (node (ref "J16") (pin "1") (pinfunction "1_1") (pintype "passive"))
      (node (ref "V1") (pin "4") (pinfunction "FIL1_4") (pintype "passive"))
    )
    (net (code "75") (name "Net-(V1C-FIL2)") (class "Default")
      (node (ref "J20") (pin "1") (pinfunction "1_1") (pintype "passive"))
      (node (ref "V1") (pin "5") (pinfunction "FIL2_5") (pintype "passive"))
    )
    (net (code "76") (name "Net-(V1C-TAP)") (class "Default")
      (node (ref "J19") (pin "1") (pinfunction "1_1") (pintype "passive"))
      (node (ref "V1") (pin "9") (pinfunction "TAP_9") (pintype "passive"))
    )
    (net (code "77") (name "unconnected-(J1-R-Pad2)") (class "Default")
      (node (ref "J1") (pin "2") (pinfunction "R_2") (pintype "passive+no_connect"))
    )
    (net (code "78") (name "unconnected-(J1-RN-Pad5)") (class "Default")
      (node (ref "J1") (pin "5") (pinfunction "RN_5") (pintype "passive+no_connect"))
    )
    (net (code "79") (name "unconnected-(J1-SN-Pad6)") (class "Default")
      (node (ref "J1") (pin "6") (pinfunction "SN_6") (pintype "passive+no_connect"))
    )
    (net (code "80") (name "unconnected-(J1-TN-Pad4)") (class "Default")
      (node (ref "J1") (pin "4") (pinfunction "TN_4") (pintype "passive+no_connect"))
    )
    (net (code "81") (name "unconnected-(J2-R-Pad2)") (class "Default")
      (node (ref "J2") (pin "2") (pinfunction "R_2") (pintype "passive+no_connect"))
    )
    (net (code "82") (name "unconnected-(J2-RN-Pad5)") (class "Default")
      (node (ref "J2") (pin "5") (pinfunction "RN_5") (pintype "passive+no_connect"))
    )
    (net (code "83") (name "unconnected-(J2-SN-Pad6)") (class "Default")
      (node (ref "J2") (pin "6") (pinfunction "SN_6") (pintype "passive+no_connect"))
    )
    (net (code "84") (name "unconnected-(J2-TN-Pad4)") (class "Default")
      (node (ref "J2") (pin "4") (pinfunction "TN_4") (pintype "passive+no_connect"))
    )
  )
)
